# cfc-sensor-card.net
KiCad netlist of a schematic drawn in EAGLE
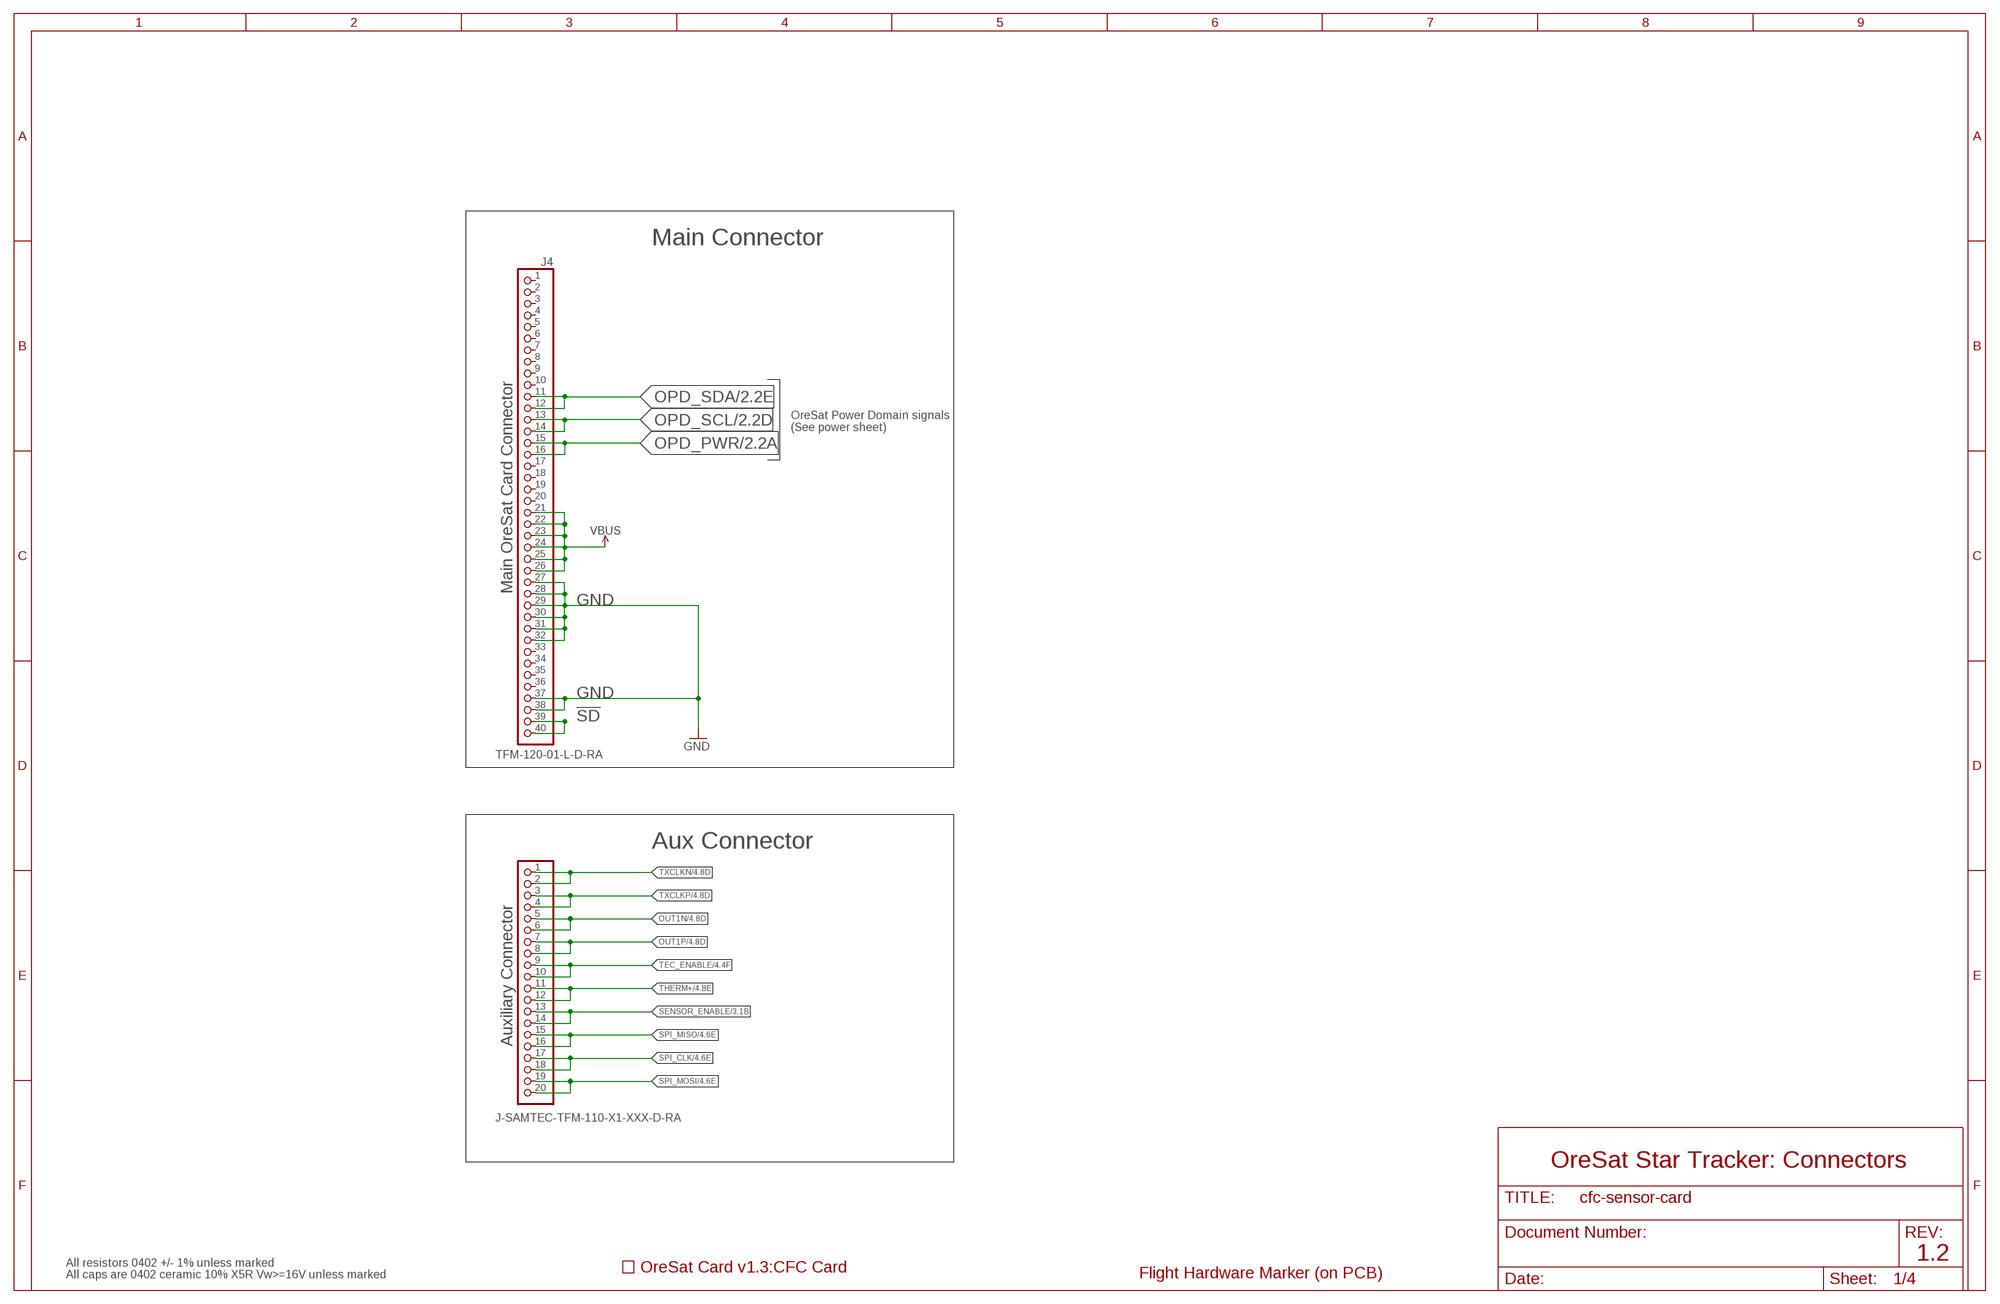
[diagram p0: schematic, sheet 1]
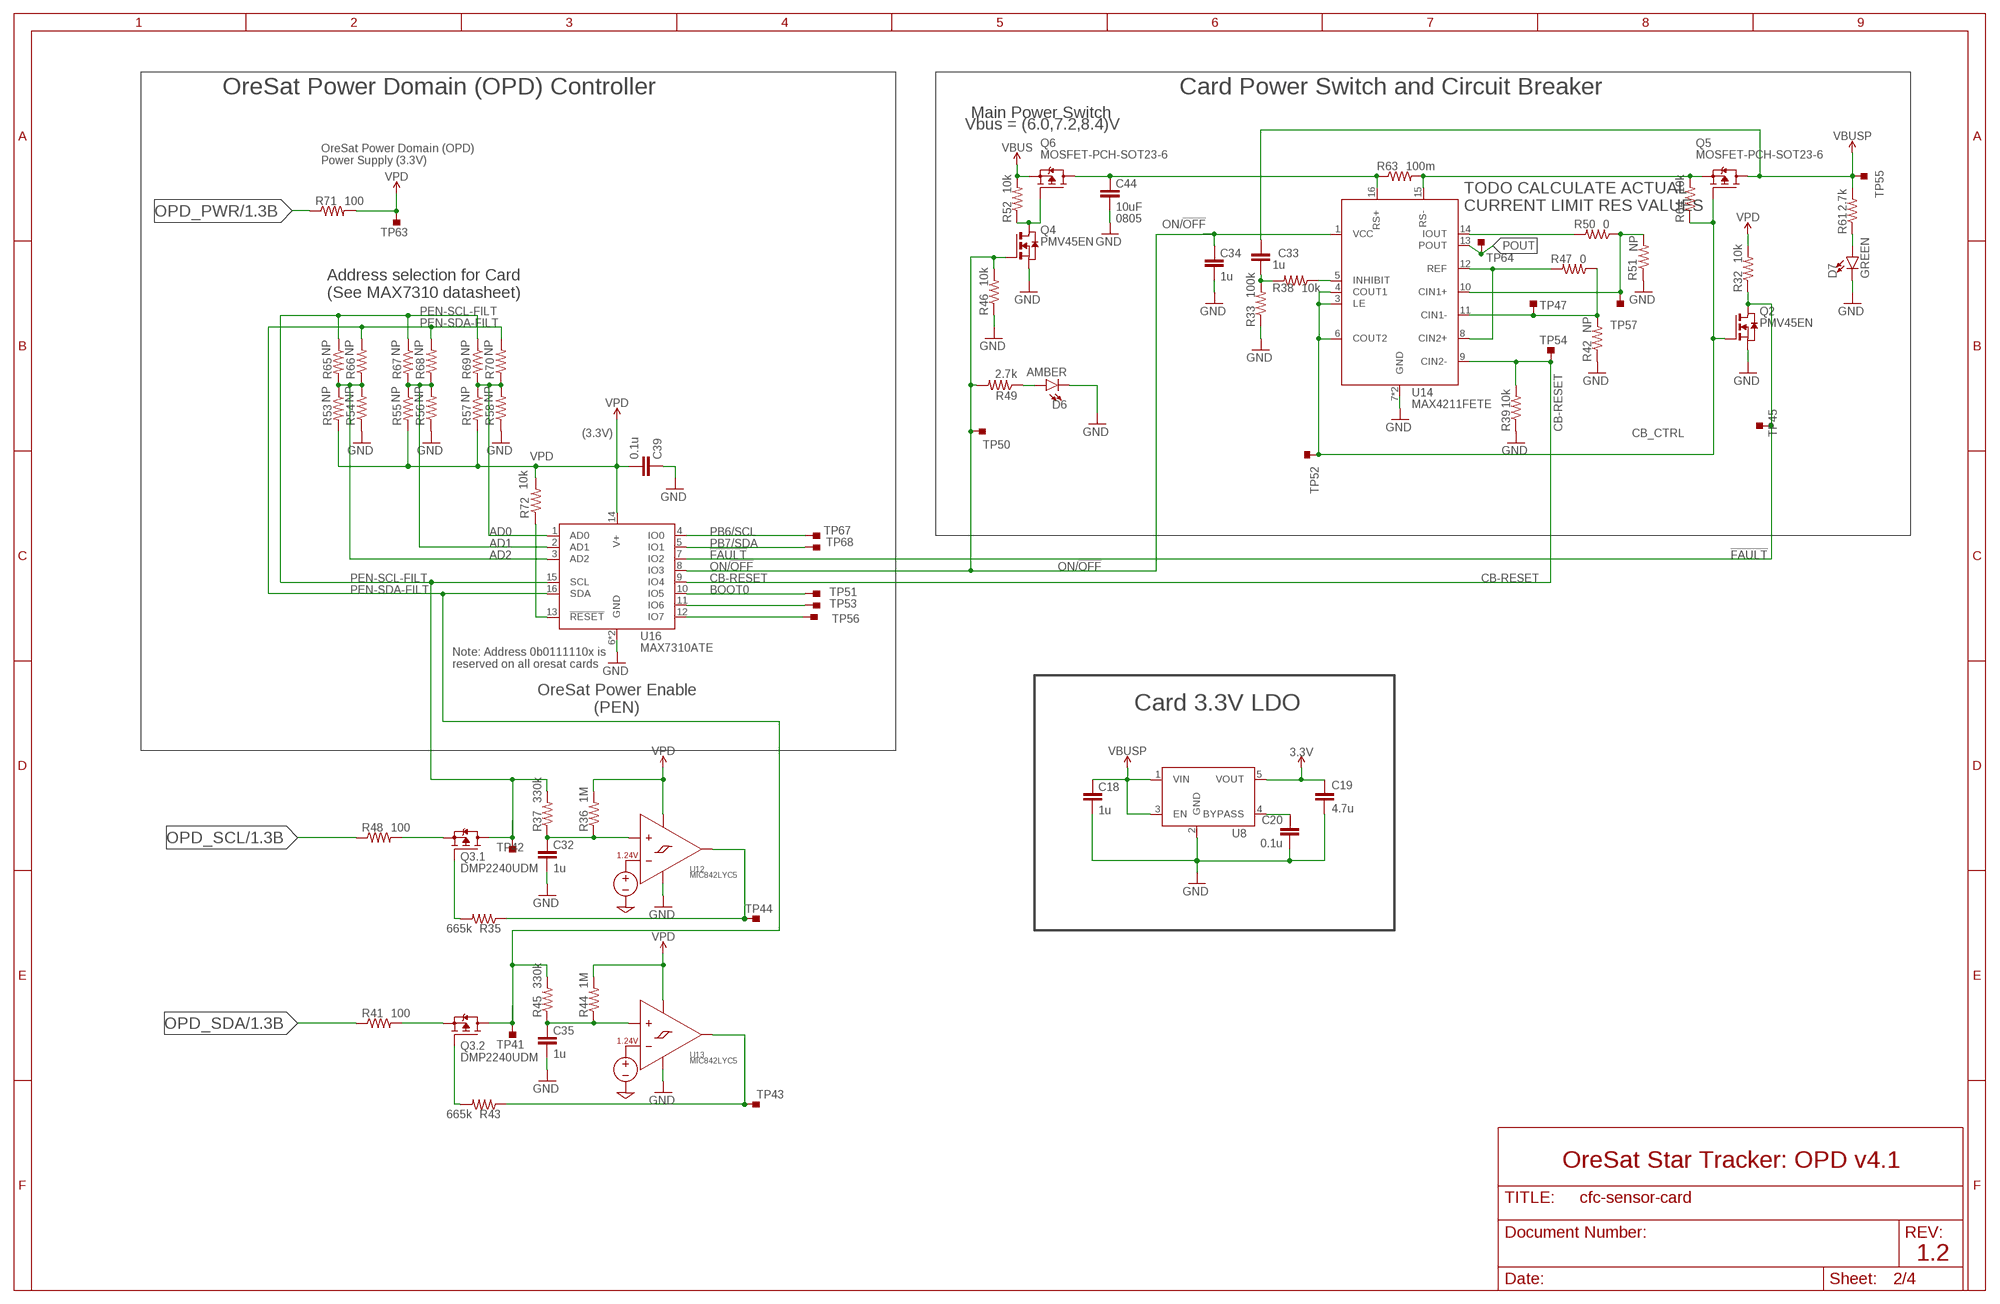
[diagram p1: schematic, sheet 2]
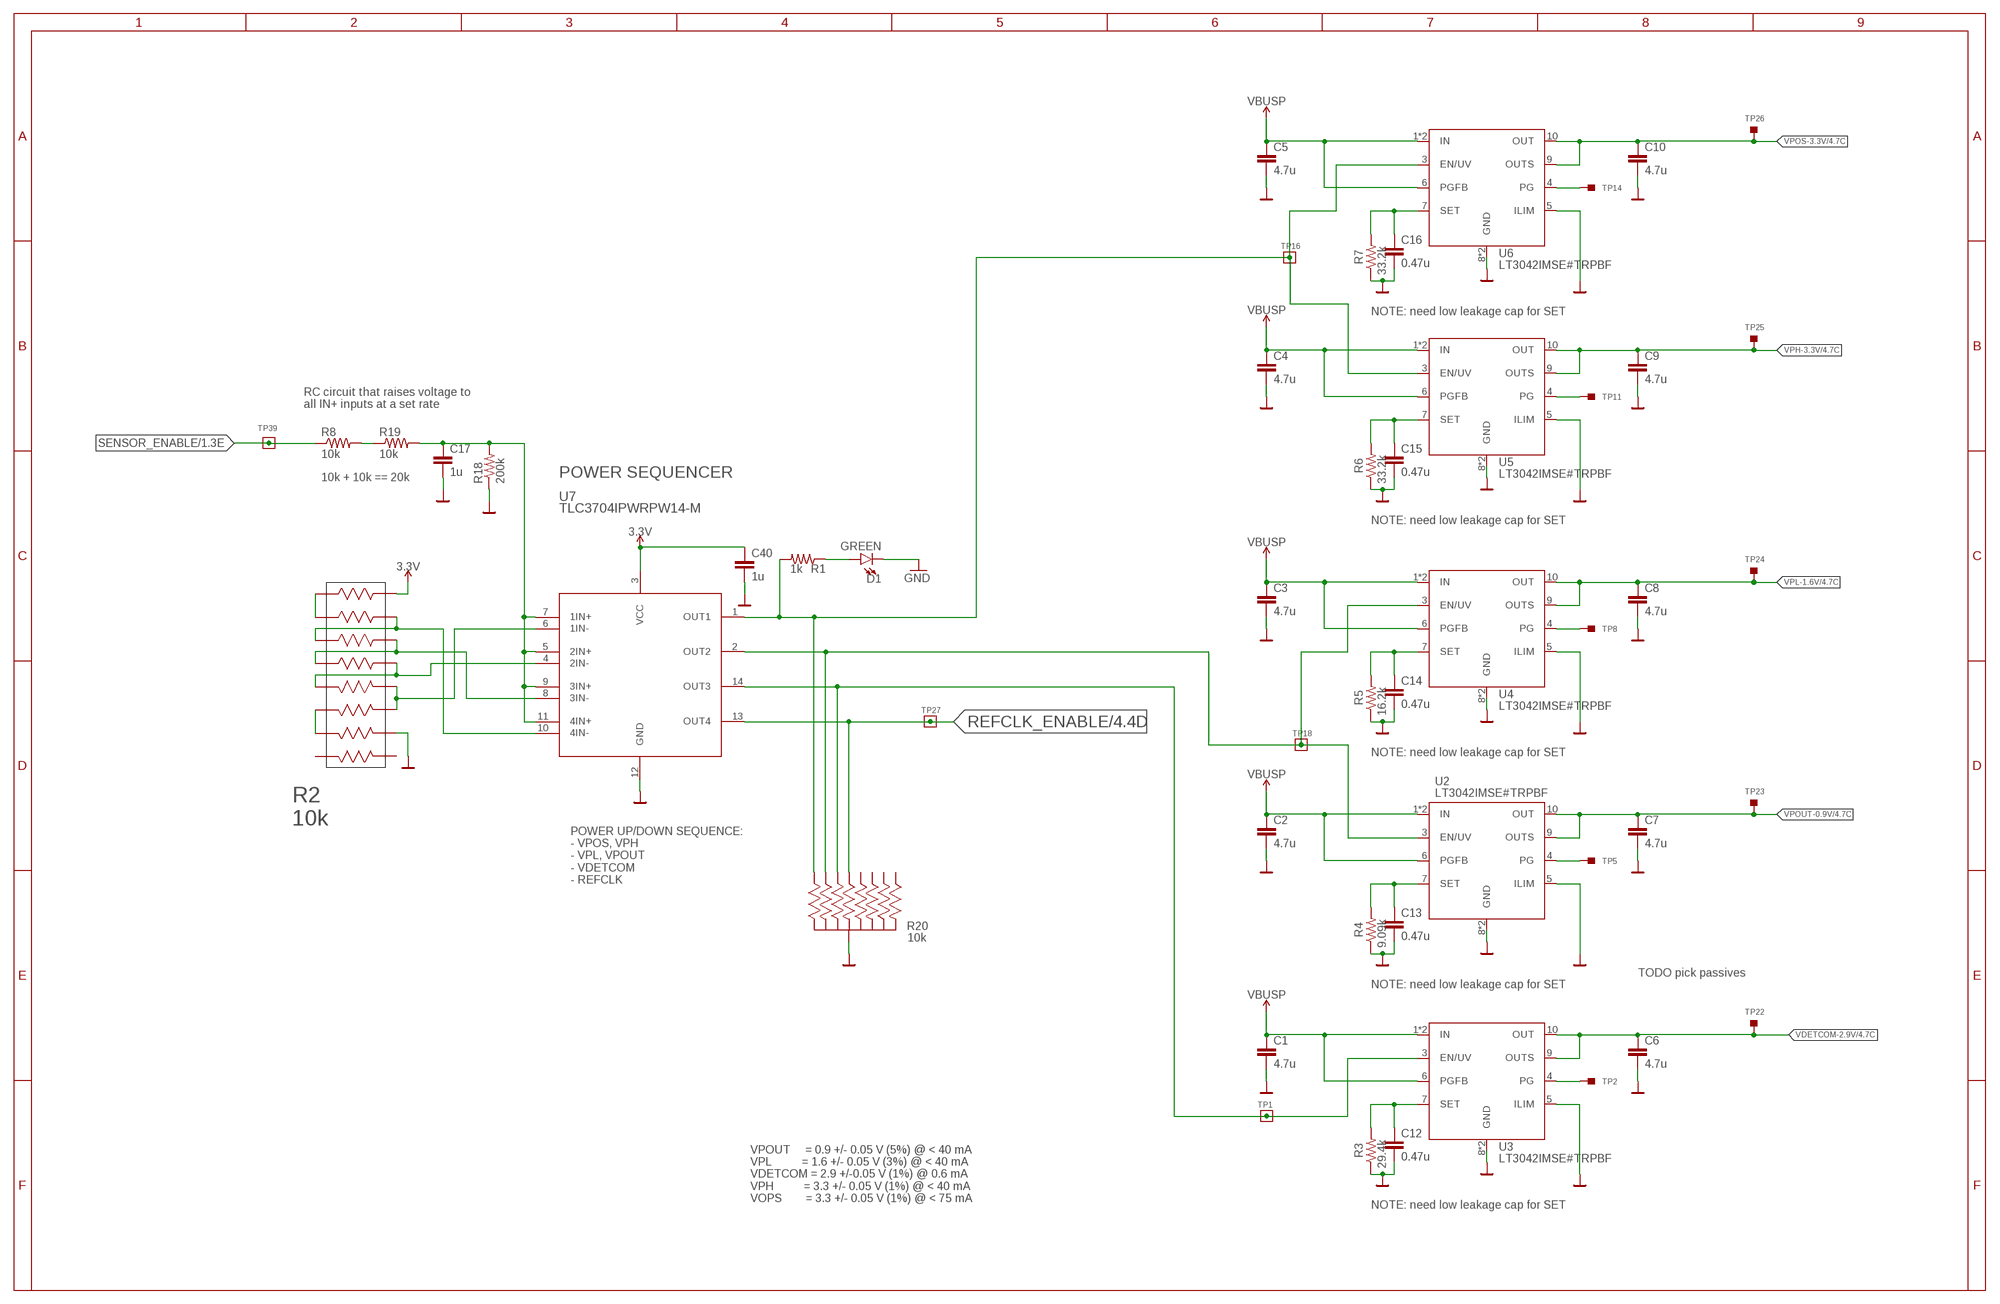
[diagram p2: schematic, sheet 3]
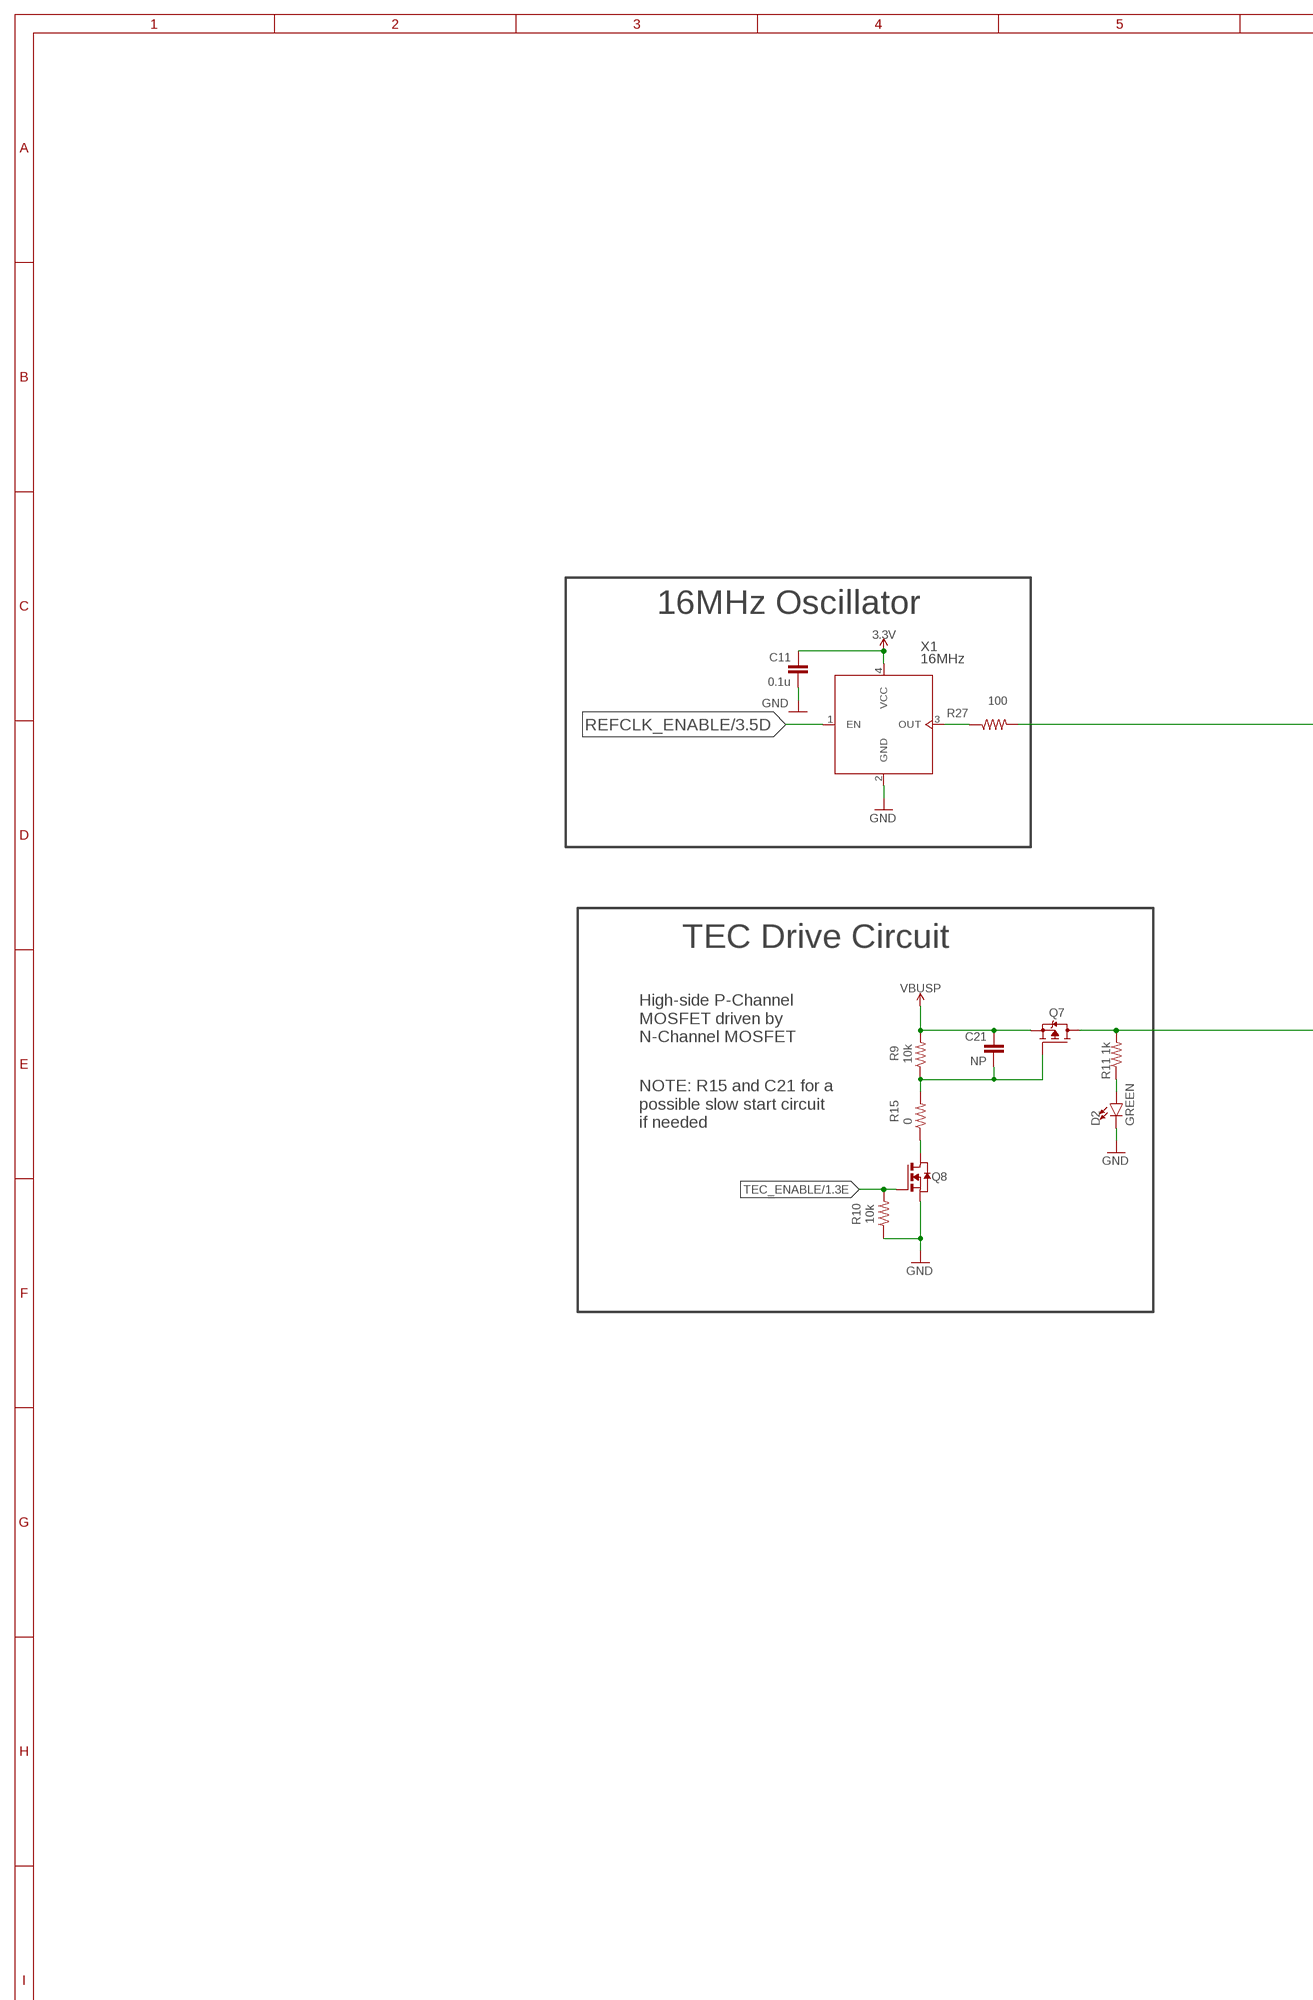
[diagram p3: schematic, sheet 4, part 1 of 2]
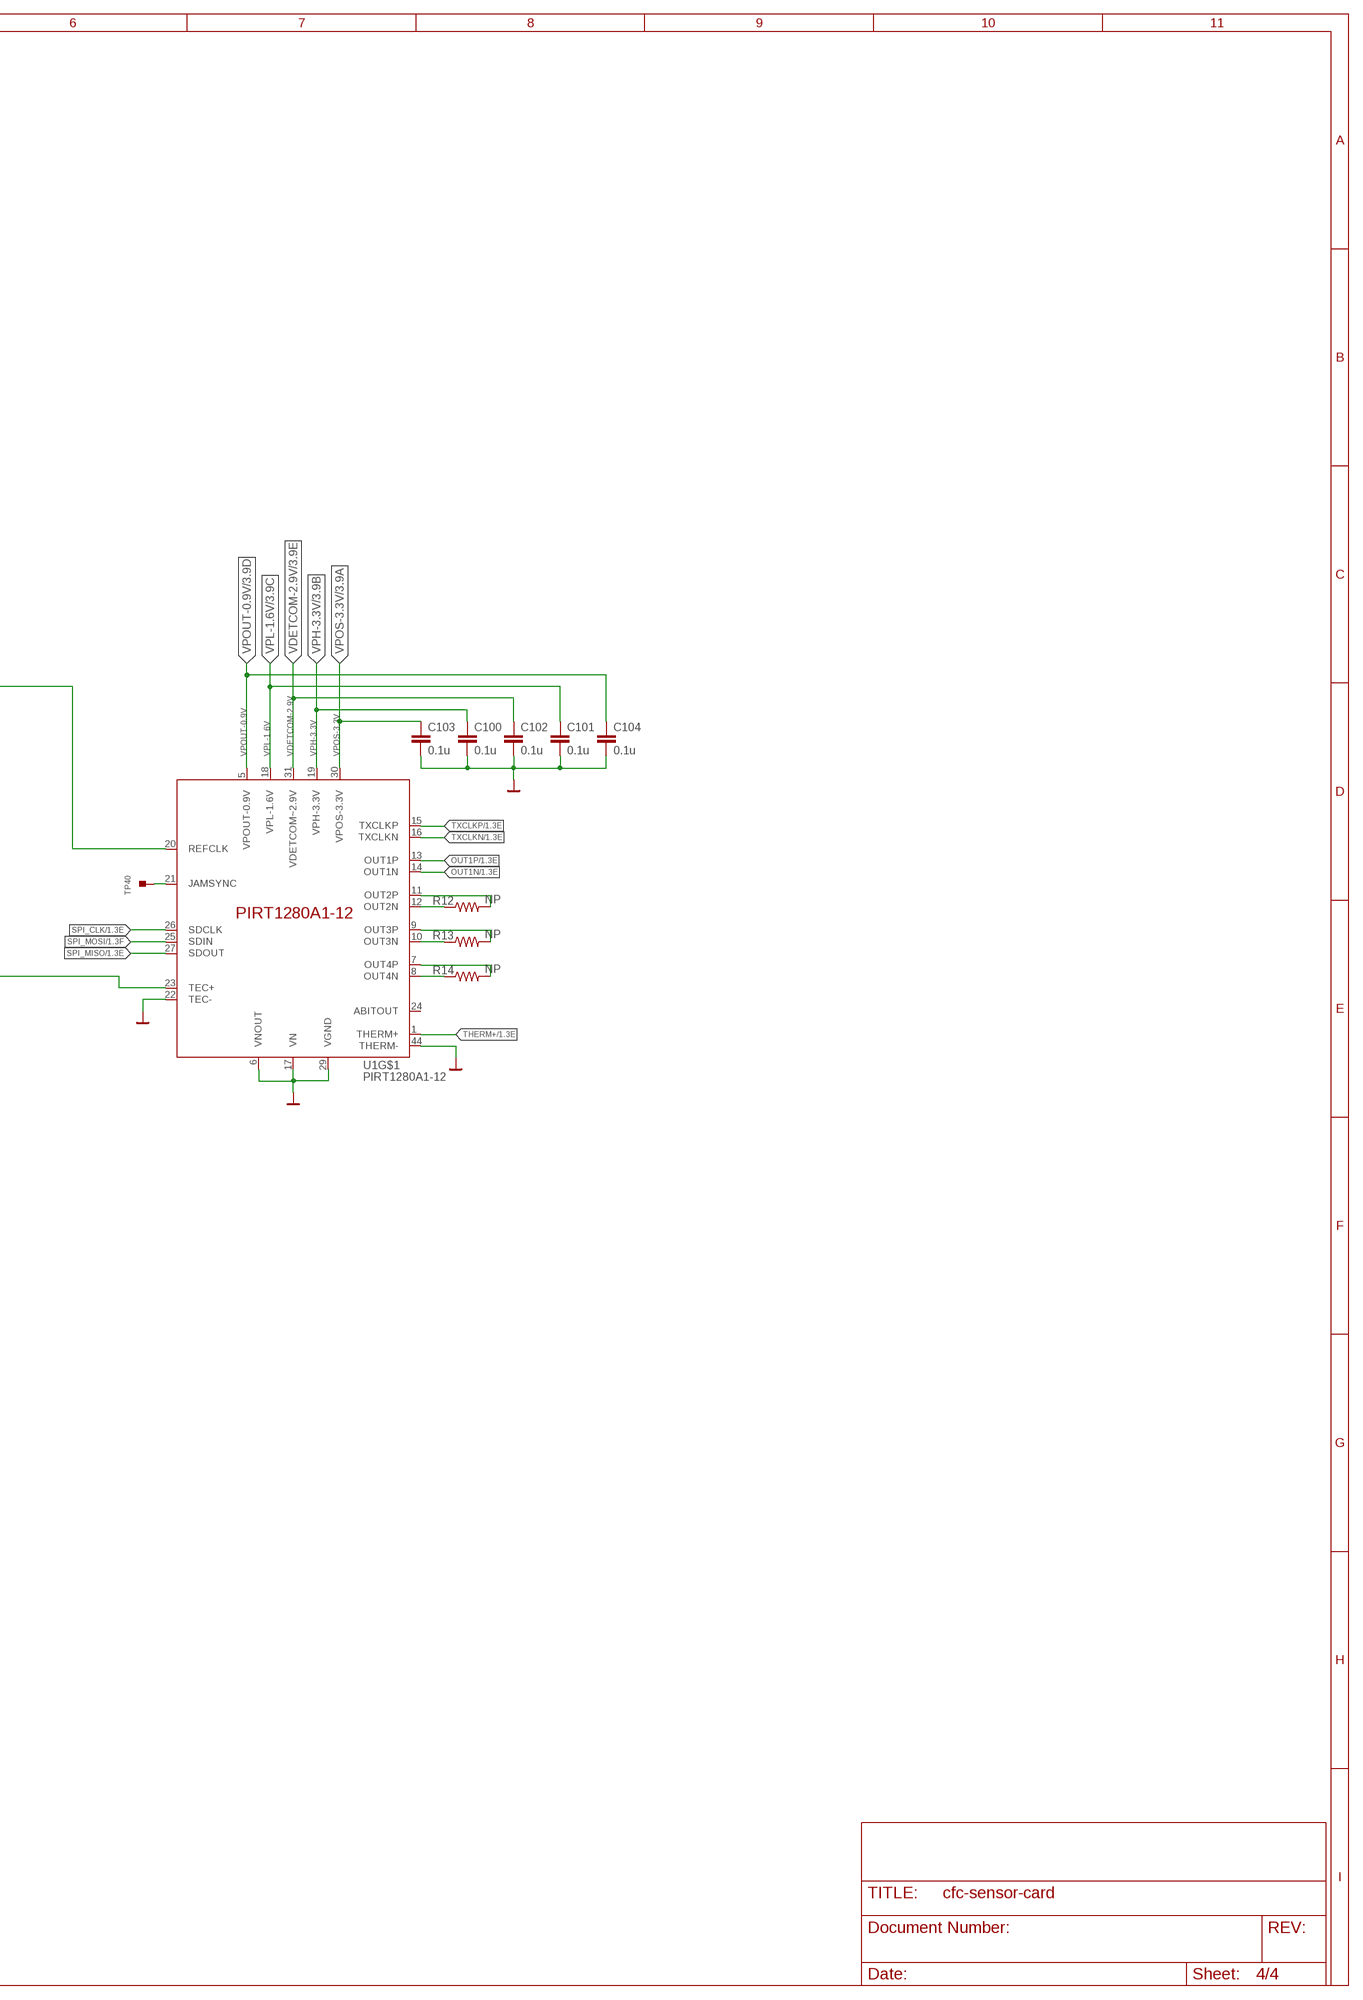
[diagram p4: schematic, sheet 4, part 2 of 2]

(export (version "E")
  (design (tool "Eeschema 10.0.6"))
  (components
    (comp (ref "C1")
      (value "4.7u")
      (footprint "eagle-import:.0603-B")
      (libsource (lib "eagle-import") (part "C-EU0603-B"))
    )
    (comp (ref "C2")
      (value "4.7u")
      (footprint "eagle-import:.0603-B")
      (libsource (lib "eagle-import") (part "C-EU0603-B"))
    )
    (comp (ref "C3")
      (value "4.7u")
      (footprint "eagle-import:.0603-B")
      (libsource (lib "eagle-import") (part "C-EU0603-B"))
    )
    (comp (ref "C4")
      (value "4.7u")
      (footprint "eagle-import:.0603-B")
      (libsource (lib "eagle-import") (part "C-EU0603-B"))
    )
    (comp (ref "C5")
      (value "4.7u")
      (footprint "eagle-import:.0603-B")
      (libsource (lib "eagle-import") (part "C-EU0603-B"))
    )
    (comp (ref "C6")
      (value "4.7u")
      (footprint "eagle-import:.0603-B")
      (libsource (lib "eagle-import") (part "C-EU0603-B"))
    )
    (comp (ref "C7")
      (value "4.7u")
      (footprint "eagle-import:.0603-B")
      (libsource (lib "eagle-import") (part "C-EU0603-B"))
    )
    (comp (ref "C8")
      (value "4.7u")
      (footprint "eagle-import:.0603-B")
      (libsource (lib "eagle-import") (part "C-EU0603-B"))
    )
    (comp (ref "C9")
      (value "4.7u")
      (footprint "eagle-import:.0603-B")
      (libsource (lib "eagle-import") (part "C-EU0603-B"))
    )
    (comp (ref "C10")
      (value "4.7u")
      (footprint "eagle-import:.0603-B")
      (libsource (lib "eagle-import") (part "C-EU0603-B"))
    )
    (comp (ref "C12")
      (value "0.47u")
      (footprint "eagle-import:.0603-B")
      (libsource (lib "eagle-import") (part "C-EU0603-B"))
    )
    (comp (ref "C13")
      (value "0.47u")
      (footprint "eagle-import:.0603-B")
      (libsource (lib "eagle-import") (part "C-EU0603-B"))
    )
    (comp (ref "C14")
      (value "0.47u")
      (footprint "eagle-import:.0603-B")
      (libsource (lib "eagle-import") (part "C-EU0603-B"))
    )
    (comp (ref "C15")
      (value "0.47u")
      (footprint "eagle-import:.0603-B")
      (libsource (lib "eagle-import") (part "C-EU0603-B"))
    )
    (comp (ref "C16")
      (value "0.47u")
      (footprint "eagle-import:.0603-B")
      (libsource (lib "eagle-import") (part "C-EU0603-B"))
    )
    (comp (ref "C17")
      (value "1u")
      (footprint "eagle-import:.0603-B")
      (libsource (lib "eagle-import") (part "C-EU0603-B"))
    )
    (comp (ref "C40")
      (value "1u")
      (footprint "eagle-import:.0603-B")
      (libsource (lib "eagle-import") (part "C-EU0603-B"))
    )
    (comp (ref "D1")
      (value "GREEN")
      (footprint "eagle-import:LED-0603")
      (description "Green 573nm LED Indication - Discrete 2V 0603 (1608 Metric)")
      (fields
        (field (name "DIGI-KEY_PART_NUMBER") "732-12017-1-ND")
        (field (name "MANUFACTURER") "Würth Elektronik")
      )
      (libsource (lib "eagle-import") (part "LED-GREEN0603"))
    )
    (comp (ref "R1")
      (value "1k")
      (footprint "eagle-import:.0603-B")
      (libsource (lib "eagle-import") (part "R-US_0603-B"))
    )
    (comp (ref "R2")
      (value "10k")
      (footprint "eagle-import:RES_EXB2HV")
      (fields (field (name "MPN") "EXB-2HV103JV"))
      (libsource (lib "eagle-import") (part "EXB-2HV103JV-LEGACY"))
    )
    (comp (ref "R3")
      (value "29.4k")
      (footprint "eagle-import:.0603-B")
      (libsource (lib "eagle-import") (part "R-US_0603-B"))
    )
    (comp (ref "R4")
      (value "9.09k")
      (footprint "eagle-import:.0603-B")
      (libsource (lib "eagle-import") (part "R-US_0603-B"))
    )
    (comp (ref "R5")
      (value "16.2k")
      (footprint "eagle-import:.0603-B")
      (libsource (lib "eagle-import") (part "R-US_0603-B"))
    )
    (comp (ref "R6")
      (value "33.2k")
      (footprint "eagle-import:.0603-B")
      (libsource (lib "eagle-import") (part "R-US_0603-B"))
    )
    (comp (ref "R7")
      (value "33.2k")
      (footprint "eagle-import:.0603-B")
      (libsource (lib "eagle-import") (part "R-US_0603-B"))
    )
    (comp (ref "R8")
      (value "10k")
      (footprint "eagle-import:.0603-B")
      (libsource (lib "eagle-import") (part "R-US_0603-B"))
    )
    (comp (ref "R18")
      (value "200k")
      (footprint "eagle-import:.0603-B")
      (libsource (lib "eagle-import") (part "R-US_0603-B"))
    )
    (comp (ref "R19")
      (value "10k")
      (footprint "eagle-import:.0603-B")
      (libsource (lib "eagle-import") (part "R-US_0603-B"))
    )
    (comp (ref "R20")
      (value "10k")
      (footprint "eagle-import:ARRAY_EXBA-M")
      (fields (field (name "MFR") "Panasonic Electronic Components") (field (name "MPN") "EXB-A10P103J"))
      (libsource (lib "eagle-import") (part "EXB-A10P391JC_ARRAY_EXBA-M"))
    )
    (comp (ref "TP1")
      (value "TEST-POINT-LARGE-SQUARE")
      (footprint "eagle-import:1X01")
      (libsource (lib "eagle-import") (part "TEST-POINT-LARGE-SQUARE"))
    )
    (comp (ref "TP2")
      (value "TEST-POINT_SMD-SMD-10SN")
      (footprint "eagle-import:TESTPOINT_SMD-10SN")
      (libsource (lib "eagle-import") (part "TEST-POINT_SMD-SMD-10SN"))
    )
    (comp (ref "TP5")
      (value "TEST-POINT_SMD-SMD-10SN")
      (footprint "eagle-import:TESTPOINT_SMD-10SN")
      (libsource (lib "eagle-import") (part "TEST-POINT_SMD-SMD-10SN"))
    )
    (comp (ref "TP8")
      (value "TEST-POINT_SMD-SMD-10SN")
      (footprint "eagle-import:TESTPOINT_SMD-10SN")
      (libsource (lib "eagle-import") (part "TEST-POINT_SMD-SMD-10SN"))
    )
    (comp (ref "TP11")
      (value "TEST-POINT_SMD-SMD-10SN")
      (footprint "eagle-import:TESTPOINT_SMD-10SN")
      (libsource (lib "eagle-import") (part "TEST-POINT_SMD-SMD-10SN"))
    )
    (comp (ref "TP14")
      (value "TEST-POINT_SMD-SMD-10SN")
      (footprint "eagle-import:TESTPOINT_SMD-10SN")
      (libsource (lib "eagle-import") (part "TEST-POINT_SMD-SMD-10SN"))
    )
    (comp (ref "TP16")
      (value "TEST-POINT-LARGE-SQUARE")
      (footprint "eagle-import:1X01")
      (libsource (lib "eagle-import") (part "TEST-POINT-LARGE-SQUARE"))
    )
    (comp (ref "TP18")
      (value "TEST-POINT-LARGE-SQUARE")
      (footprint "eagle-import:1X01")
      (libsource (lib "eagle-import") (part "TEST-POINT-LARGE-SQUARE"))
    )
    (comp (ref "TP22")
      (value "TEST-POINT_SMD-SMD-10SN")
      (footprint "eagle-import:TESTPOINT_SMD-10SN")
      (libsource (lib "eagle-import") (part "TEST-POINT_SMD-SMD-10SN"))
    )
    (comp (ref "TP23")
      (value "TEST-POINT_SMD-SMD-10SN")
      (footprint "eagle-import:TESTPOINT_SMD-10SN")
      (libsource (lib "eagle-import") (part "TEST-POINT_SMD-SMD-10SN"))
    )
    (comp (ref "TP24")
      (value "TEST-POINT_SMD-SMD-10SN")
      (footprint "eagle-import:TESTPOINT_SMD-10SN")
      (libsource (lib "eagle-import") (part "TEST-POINT_SMD-SMD-10SN"))
    )
    (comp (ref "TP25")
      (value "TEST-POINT_SMD-SMD-10SN")
      (footprint "eagle-import:TESTPOINT_SMD-10SN")
      (libsource (lib "eagle-import") (part "TEST-POINT_SMD-SMD-10SN"))
    )
    (comp (ref "TP26")
      (value "TEST-POINT_SMD-SMD-10SN")
      (footprint "eagle-import:TESTPOINT_SMD-10SN")
      (libsource (lib "eagle-import") (part "TEST-POINT_SMD-SMD-10SN"))
    )
    (comp (ref "TP27")
      (value "TEST-POINT-LARGE-SQUARE")
      (footprint "eagle-import:1X01")
      (libsource (lib "eagle-import") (part "TEST-POINT-LARGE-SQUARE"))
    )
    (comp (ref "TP39")
      (value "TEST-POINT-LARGE-SQUARE")
      (footprint "eagle-import:1X01")
      (libsource (lib "eagle-import") (part "TEST-POINT-LARGE-SQUARE"))
    )
    (comp (ref "U2")
      (value "LT3042IMSE#TRPBF")
      (footprint "eagle-import:SOP50P490X110-11N")
      (fields (field (name "MF") "Analog Devices"))
      (libsource (lib "eagle-import") (part "LT3042IMSE#TRPBF"))
    )
    (comp (ref "U3")
      (value "LT3042IMSE#TRPBF")
      (footprint "eagle-import:SOP50P490X110-11N")
      (fields (field (name "MF") "Analog Devices"))
      (libsource (lib "eagle-import") (part "LT3042IMSE#TRPBF"))
    )
    (comp (ref "U4")
      (value "LT3042IMSE#TRPBF")
      (footprint "eagle-import:SOP50P490X110-11N")
      (fields (field (name "MF") "Analog Devices"))
      (libsource (lib "eagle-import") (part "LT3042IMSE#TRPBF"))
    )
    (comp (ref "U5")
      (value "LT3042IMSE#TRPBF")
      (footprint "eagle-import:SOP50P490X110-11N")
      (fields (field (name "MF") "Analog Devices"))
      (libsource (lib "eagle-import") (part "LT3042IMSE#TRPBF"))
    )
    (comp (ref "U6")
      (value "LT3042IMSE#TRPBF")
      (footprint "eagle-import:SOP50P490X110-11N")
      (fields (field (name "MF") "Analog Devices"))
      (libsource (lib "eagle-import") (part "LT3042IMSE#TRPBF"))
    )
    (comp (ref "U7")
      (value "TLC3704IPWRPW14-M")
      (footprint "eagle-import:14-TSSOP")
      (fields
        (field (name "GENERIC_PART_NUMBER") "LM2901-Q1")
        (field (name "MANUFACTURER") "Texas Instruments")
        (field (name "MPN") "LM2901QPWRQ1")
      )
      (libsource (lib "eagle-import") (part "TLC3704IPWRPW14-M"))
    )
    (comp (ref "C18")
      (value "1u")
      (footprint "eagle-import:.0603-B")
      (libsource (lib "eagle-import") (part "C-EU0603-B"))
    )
    (comp (ref "C19")
      (value "4.7u")
      (footprint "eagle-import:.0603-B")
      (libsource (lib "eagle-import") (part "C-EU0603-B"))
    )
    (comp (ref "C20")
      (value "0.1u")
      (footprint "eagle-import:.0603-B")
      (libsource (lib "eagle-import") (part "C-EU0603-B"))
    )
    (comp (ref "C32")
      (value "1u")
      (footprint "eagle-import:.0603-B")
      (libsource (lib "eagle-import") (part "C-EU0603-B"))
    )
    (comp (ref "C33")
      (value "1u")
      (footprint "eagle-import:.0603-B")
      (libsource (lib "eagle-import") (part "C-EU0603-B"))
    )
    (comp (ref "C34")
      (value "1u")
      (footprint "eagle-import:.0603-B")
      (libsource (lib "eagle-import") (part "C-EU0603-B"))
    )
    (comp (ref "C35")
      (value "1u")
      (footprint "eagle-import:.0603-B")
      (libsource (lib "eagle-import") (part "C-EU0603-B"))
    )
    (comp (ref "C39")
      (value "0.1u")
      (footprint "eagle-import:.0603-B")
      (libsource (lib "eagle-import") (part "C-EU0603-B"))
    )
    (comp (ref "C44")
      (value "10uF")
      (footprint "eagle-import:.0603-B")
      (libsource (lib "eagle-import") (part "C-EU0603-B"))
    )
    (comp (ref "D6")
      (value "AMBER")
      (footprint "eagle-import:LED-0603")
      (libsource (lib "eagle-import") (part "SparkFun-LED_529_LED-GREEN0603"))
    )
    (comp (ref "D7")
      (value "GREEN")
      (footprint "eagle-import:LED-0603")
      (libsource (lib "eagle-import") (part "LED-GREEN0603"))
    )
    (comp (ref "Q2")
      (value "PMV45EN")
      (footprint "eagle-import:SOT23")
      (fields (field (name "MPN") "PMV45EN2R"))
      (libsource (lib "eagle-import") (part "PMV45EN"))
    )
    (comp (ref "Q3")
      (value "DMP2240UDM")
      (footprint "eagle-import:SOT23-6")
      (fields (field (name "MFR") "Diodes Inc") (field (name "MPN") "DMP2240UDM-7"))
      (libsource (lib "eagle-import") (part "Q-MOSFET-PCH-dual-SOT23-6_MOSFET-PCH-SOT23-6"))
    )
    (comp (ref "Q4")
      (value "PMV45EN")
      (footprint "eagle-import:SOT23")
      (fields (field (name "MPN") "PMV45EN2R"))
      (libsource (lib "eagle-import") (part "PMV45EN"))
    )
    (comp (ref "Q5")
      (value "MOSFET-PCH-SOT23-6")
      (footprint "eagle-import:SOT23-6")
      (fields (field (name "MPN") "DMP3050LVT-7") (field (name "MPN_1") "DMP3050LVT-7"))
      (libsource (lib "eagle-import") (part "MOSFET-PCH-SOT23-6"))
    )
    (comp (ref "Q6")
      (value "MOSFET-PCH-SOT23-6")
      (footprint "eagle-import:SOT23-6")
      (fields (field (name "MPN") "DMP3050LVT-7") (field (name "MPN_1") "DMP3050LVT-7"))
      (libsource (lib "eagle-import") (part "MOSFET-PCH-SOT23-6"))
    )
    (comp (ref "R32")
      (value "10k")
      (footprint "eagle-import:.0603-B")
      (libsource (lib "eagle-import") (part "R-US_0603-B"))
    )
    (comp (ref "R33")
      (value "100k")
      (footprint "eagle-import:.0603-B")
      (fields (field (name "MFR") "Samsung") (field (name "MPN") "RC1005F6653CS"))
      (libsource (lib "eagle-import") (part "R-US_0603-B"))
    )
    (comp (ref "R35")
      (value "665k")
      (footprint "eagle-import:.0603-B")
      (libsource (lib "eagle-import") (part "R-US_0603-B"))
    )
    (comp (ref "R36")
      (value "1M")
      (footprint "eagle-import:.0603-B")
      (libsource (lib "eagle-import") (part "R-US_0603-B"))
    )
    (comp (ref "R37")
      (value "330k")
      (footprint "eagle-import:.0603-B")
      (libsource (lib "eagle-import") (part "R-US_0603-B"))
    )
    (comp (ref "R38")
      (value "10k")
      (footprint "eagle-import:.0603-B")
      (fields (field (name "MFR") "Samsung") (field (name "MPN") "RC1005F6653CS"))
      (libsource (lib "eagle-import") (part "R-US_0603-B"))
    )
    (comp (ref "R39")
      (value "10k")
      (footprint "eagle-import:.0603-B")
      (libsource (lib "eagle-import") (part "R-US_0603-B"))
    )
    (comp (ref "R41")
      (value "100")
      (footprint "eagle-import:.0603-B")
      (libsource (lib "eagle-import") (part "R-US_0603-B"))
    )
    (comp (ref "R42")
      (value "NP")
      (footprint "eagle-import:.0603-B")
      (fields (field (name "MFR") "Samsung") (field (name "MPN") "RC1005F6653CS"))
      (libsource (lib "eagle-import") (part "R-US_0603-B"))
    )
    (comp (ref "R43")
      (value "665k")
      (footprint "eagle-import:.0603-B")
      (libsource (lib "eagle-import") (part "R-US_0603-B"))
    )
    (comp (ref "R44")
      (value "1M")
      (footprint "eagle-import:.0603-B")
      (libsource (lib "eagle-import") (part "R-US_0603-B"))
    )
    (comp (ref "R45")
      (value "330k")
      (footprint "eagle-import:.0603-B")
      (libsource (lib "eagle-import") (part "R-US_0603-B"))
    )
    (comp (ref "R46")
      (value "10k")
      (footprint "eagle-import:.0603-B")
      (libsource (lib "eagle-import") (part "R-US_0603-B"))
    )
    (comp (ref "R47")
      (value "0")
      (footprint "eagle-import:.0603-B")
      (libsource (lib "eagle-import") (part "R-US_0603-B"))
    )
    (comp (ref "R48")
      (value "100")
      (footprint "eagle-import:.0603-B")
      (libsource (lib "eagle-import") (part "R-US_0603-B"))
    )
    (comp (ref "R49")
      (value "2.7k")
      (footprint "eagle-import:.0603-B")
      (libsource (lib "eagle-import") (part "R-US_0603-B"))
    )
    (comp (ref "R50")
      (value "0")
      (footprint "eagle-import:.0603-B")
      (libsource (lib "eagle-import") (part "R-US_0603-B"))
    )
    (comp (ref "R51")
      (value "NP")
      (footprint "eagle-import:.0603-B")
      (fields (field (name "MFR") "Samsung") (field (name "MPN") "RC1005F6653CS"))
      (libsource (lib "eagle-import") (part "R-US_0603-B"))
    )
    (comp (ref "R52")
      (value "10k")
      (footprint "eagle-import:.0603-B")
      (libsource (lib "eagle-import") (part "R-US_0603-B"))
    )
    (comp (ref "R53")
      (value "NP")
      (footprint "eagle-import:.0603-B")
      (fields (field (name "MFR") "Samsung") (field (name "MPN") "RC1005F6653CS"))
      (libsource (lib "eagle-import") (part "R-US_0603-B"))
    )
    (comp (ref "R54")
      (value "NP")
      (footprint "eagle-import:.0603-B")
      (fields (field (name "MFR") "Samsung") (field (name "MPN") "RC1005F6653CS"))
      (libsource (lib "eagle-import") (part "R-US_0603-B"))
    )
    (comp (ref "R55")
      (value "NP")
      (footprint "eagle-import:.0603-B")
      (fields (field (name "MFR") "Samsung") (field (name "MPN") "RC1005F6653CS"))
      (libsource (lib "eagle-import") (part "R-US_0603-B"))
    )
    (comp (ref "R56")
      (value "NP")
      (footprint "eagle-import:.0603-B")
      (fields (field (name "MFR") "Samsung") (field (name "MPN") "RC1005F6653CS"))
      (libsource (lib "eagle-import") (part "R-US_0603-B"))
    )
    (comp (ref "R57")
      (value "NP")
      (footprint "eagle-import:.0603-B")
      (fields (field (name "MFR") "Samsung") (field (name "MPN") "RC1005F6653CS"))
      (libsource (lib "eagle-import") (part "R-US_0603-B"))
    )
    (comp (ref "R58")
      (value "NP")
      (footprint "eagle-import:.0603-B")
      (fields (field (name "MFR") "Samsung") (field (name "MPN") "RC1005F6653CS"))
      (libsource (lib "eagle-import") (part "R-US_0603-B"))
    )
    (comp (ref "R61")
      (value "2.7k")
      (footprint "eagle-import:.0603-B")
      (libsource (lib "eagle-import") (part "R-US_0603-B"))
    )
    (comp (ref "R63")
      (value "100m")
      (footprint "eagle-import:R1206")
      (libsource (lib "eagle-import") (part "rcl_334_R-US_R1206"))
    )
    (comp (ref "R64")
      (value "10k")
      (footprint "eagle-import:.0603-B")
      (libsource (lib "eagle-import") (part "R-US_0603-B"))
    )
    (comp (ref "R65")
      (value "NP")
      (footprint "eagle-import:.0603-B")
      (fields (field (name "MFR") "Samsung") (field (name "MPN") "RC1005F6653CS"))
      (libsource (lib "eagle-import") (part "R-US_0603-B"))
    )
    (comp (ref "R66")
      (value "NP")
      (footprint "eagle-import:.0603-B")
      (fields (field (name "MFR") "Samsung") (field (name "MPN") "RC1005F6653CS"))
      (libsource (lib "eagle-import") (part "R-US_0603-B"))
    )
    (comp (ref "R67")
      (value "NP")
      (footprint "eagle-import:.0603-B")
      (fields (field (name "MFR") "Samsung") (field (name "MPN") "RC1005F6653CS"))
      (libsource (lib "eagle-import") (part "R-US_0603-B"))
    )
    (comp (ref "R68")
      (value "NP")
      (footprint "eagle-import:.0603-B")
      (fields (field (name "MFR") "Samsung") (field (name "MPN") "RC1005F6653CS"))
      (libsource (lib "eagle-import") (part "R-US_0603-B"))
    )
    (comp (ref "R69")
      (value "NP")
      (footprint "eagle-import:.0603-B")
      (fields (field (name "MFR") "Samsung") (field (name "MPN") "RC1005F6653CS"))
      (libsource (lib "eagle-import") (part "R-US_0603-B"))
    )
    (comp (ref "R70")
      (value "NP")
      (footprint "eagle-import:.0603-B")
      (fields (field (name "MFR") "Samsung") (field (name "MPN") "RC1005F6653CS"))
      (libsource (lib "eagle-import") (part "R-US_0603-B"))
    )
    (comp (ref "R71")
      (value "100")
      (footprint "eagle-import:.0603-B")
      (libsource (lib "eagle-import") (part "R-US_0603-B"))
    )
    (comp (ref "R72")
      (value "10k")
      (footprint "eagle-import:.0603-B")
      (libsource (lib "eagle-import") (part "R-US_0603-B"))
    )
    (comp (ref "TP41")
      (value "TEST-POINT_SMD-SMD-10SN")
      (footprint "eagle-import:TESTPOINT_SMD-10SN")
      (libsource (lib "eagle-import") (part "TEST-POINT_SMD-SMD-10SN"))
    )
    (comp (ref "TP42")
      (value "TEST-POINT_SMD-SMD-10SN")
      (footprint "eagle-import:TESTPOINT_SMD-10SN")
      (libsource (lib "eagle-import") (part "TEST-POINT_SMD-SMD-10SN"))
    )
    (comp (ref "TP43")
      (value "TEST-POINT_SMD-SMD-10SN")
      (footprint "eagle-import:TESTPOINT_SMD-10SN")
      (libsource (lib "eagle-import") (part "TEST-POINT_SMD-SMD-10SN"))
    )
    (comp (ref "TP44")
      (value "TEST-POINT_SMD-SMD-10SN")
      (footprint "eagle-import:TESTPOINT_SMD-10SN")
      (libsource (lib "eagle-import") (part "TEST-POINT_SMD-SMD-10SN"))
    )
    (comp (ref "TP45")
      (value "TEST-POINT_SMD-SMD-10SN")
      (footprint "eagle-import:TESTPOINT_SMD-10SN")
      (libsource (lib "eagle-import") (part "TEST-POINT_SMD-SMD-10SN"))
    )
    (comp (ref "TP47")
      (value "TEST-POINT_SMD-SMD-10SN")
      (footprint "eagle-import:TESTPOINT_SMD-10SN")
      (libsource (lib "eagle-import") (part "TEST-POINT_SMD-SMD-10SN"))
    )
    (comp (ref "TP50")
      (value "TEST-POINT_SMD-SMD-10SN")
      (footprint "eagle-import:TESTPOINT_SMD-10SN")
      (libsource (lib "eagle-import") (part "TEST-POINT_SMD-SMD-10SN"))
    )
    (comp (ref "TP51")
      (value "TEST-POINT_SMD-SMD-10SN")
      (footprint "eagle-import:TESTPOINT_SMD-10SN")
      (libsource (lib "eagle-import") (part "TEST-POINT_SMD-SMD-10SN"))
    )
    (comp (ref "TP52")
      (value "TEST-POINT_SMD-SMD-10SN")
      (footprint "eagle-import:TESTPOINT_SMD-10SN")
      (libsource (lib "eagle-import") (part "TEST-POINT_SMD-SMD-10SN"))
    )
    (comp (ref "TP53")
      (value "TEST-POINT_SMD-SMD-10SN")
      (footprint "eagle-import:TESTPOINT_SMD-10SN")
      (libsource (lib "eagle-import") (part "TEST-POINT_SMD-SMD-10SN"))
    )
    (comp (ref "TP54")
      (value "TEST-POINT_SMD-SMD-10SN")
      (footprint "eagle-import:TESTPOINT_SMD-10SN")
      (libsource (lib "eagle-import") (part "TEST-POINT_SMD-SMD-10SN"))
    )
    (comp (ref "TP55")
      (value "TEST-POINT_SMD-SMD-10SN")
      (footprint "eagle-import:TESTPOINT_SMD-10SN")
      (libsource (lib "eagle-import") (part "TEST-POINT_SMD-SMD-10SN"))
    )
    (comp (ref "TP56")
      (value "TEST-POINT_SMD-SMD-10SN")
      (footprint "eagle-import:TESTPOINT_SMD-10SN")
      (libsource (lib "eagle-import") (part "TEST-POINT_SMD-SMD-10SN"))
    )
    (comp (ref "TP57")
      (value "TEST-POINT_SMD-SMD-10SN")
      (footprint "eagle-import:TESTPOINT_SMD-10SN")
      (libsource (lib "eagle-import") (part "TEST-POINT_SMD-SMD-10SN"))
    )
    (comp (ref "TP63")
      (value "TEST-POINT_SMD-SMD-10SN")
      (footprint "eagle-import:TESTPOINT_SMD-10SN")
      (libsource (lib "eagle-import") (part "TEST-POINT_SMD-SMD-10SN"))
    )
    (comp (ref "TP64")
      (value "TEST-POINT_SMD-SMD-10SN")
      (footprint "eagle-import:TESTPOINT_SMD-10SN")
      (libsource (lib "eagle-import") (part "TEST-POINT_SMD-SMD-10SN"))
    )
    (comp (ref "TP67")
      (value "TEST-POINT_SMD-SMD-10SN")
      (footprint "eagle-import:TESTPOINT_SMD-10SN")
      (libsource (lib "eagle-import") (part "TEST-POINT_SMD-SMD-10SN"))
    )
    (comp (ref "TP68")
      (value "TEST-POINT_SMD-SMD-10SN")
      (footprint "eagle-import:TESTPOINT_SMD-10SN")
      (libsource (lib "eagle-import") (part "TEST-POINT_SMD-SMD-10SN"))
    )
    (comp (ref "U8")
      (value "LP2985AIM5-3.3_NOPB")
      (footprint "eagle-import:SOT-23")
      (fields
        (field (name "MANUFACTURER_PART_NUMBER") "LP2985AIM5-3.3/NOPB")
        (field (name "MOUSER_PART_NUMBER") "926-2985AIM53.3/NOPB")
        (field (name "RS_PART_NUMBER") "6520033P")
      )
      (libsource (lib "eagle-import") (part "LP2985AIM5-3.3_NOPB"))
    )
    (comp (ref "U12")
      (value "MIC842LYC5")
      (footprint "eagle-import:SC70-5")
      (libsource (lib "eagle-import") (part "MIC842LYC5"))
    )
    (comp (ref "U13")
      (value "MIC842LYC5")
      (footprint "eagle-import:SC70-5")
      (libsource (lib "eagle-import") (part "MIC842LYC5"))
    )
    (comp (ref "U14")
      (value "MAX4211FETE")
      (footprint "eagle-import:QFN65P400X400X80-17T210")
      (fields (field (name "MPN") "MAX4211FETE+"))
      (libsource (lib "eagle-import") (part "MAX4211"))
    )
    (comp (ref "U16")
      (value "MAX7310ATE")
      (footprint "eagle-import:QFN65P400X400X80-17T210")
      (fields
        (field (name "MPN") "MAX7310ATE+")
        (field (name "MFR") "Maxim")
        (field (name "MPN_1") "MAX7310ATE")
      )
      (libsource (lib "eagle-import") (part "MAX7310"))
    )
    (comp (ref "J2")
      (value "J-SAMTEC-TFM-110-X1-XXX-D-RA")
      (footprint "eagle-import:J-SAMTEC-TFM-110-X1-XXX-D-RA")
      (fields (field (name "MFR") "Samtec") (field (name "MPN") "TFM-110-01-L-D-RA "))
      (libsource (lib "eagle-import") (part "J-SAMTEC-TFM-110-X1-XXX-D-RA"))
    )
    (comp (ref "J4")
      (value "TFM-120-01-L-D-RA")
      (footprint "eagle-import:J-SAMTEC-TFM-120-X1-XXX-D-RA")
      (libsource (lib "eagle-import") (part "J-SAMTEC-TFM-120-X1-XXX-D-RA"))
    )
    (comp (ref "PCB1")
      (value "ORESAT-CARD-V1.3-CFC")
      (footprint "eagle-import:ORESAT-CARD-V1.3-CFC")
      (libsource (lib "eagle-import") (part "ORESAT-CARD-V1.3-CFC"))
    )
    (comp (ref "U$1")
      (value "FLIGHMARKERNEW")
      (footprint "eagle-import:FLIGHTMARKER_NEW_BOARDS")
      (libsource (lib "eagle-import") (part "FLIGHMARKERNEW"))
    )
    (comp (ref "C11")
      (value "0.1u")
      (footprint "eagle-import:.0603-B")
      (libsource (lib "eagle-import") (part "C-EU0603-B"))
    )
    (comp (ref "C21")
      (value "NP")
      (footprint "eagle-import:.0603-B")
      (libsource (lib "eagle-import") (part "C-EU0603-B"))
    )
    (comp (ref "C100")
      (value "0.1u")
      (footprint "eagle-import:.0603-B")
      (libsource (lib "eagle-import") (part "C-EU0603-B"))
    )
    (comp (ref "C101")
      (value "0.1u")
      (footprint "eagle-import:.0603-B")
      (libsource (lib "eagle-import") (part "C-EU0603-B"))
    )
    (comp (ref "C102")
      (value "0.1u")
      (footprint "eagle-import:.0603-B")
      (libsource (lib "eagle-import") (part "C-EU0603-B"))
    )
    (comp (ref "C103")
      (value "0.1u")
      (footprint "eagle-import:.0603-B")
      (libsource (lib "eagle-import") (part "C-EU0603-B"))
    )
    (comp (ref "C104")
      (value "0.1u")
      (footprint "eagle-import:.0603-B")
      (libsource (lib "eagle-import") (part "C-EU0603-B"))
    )
    (comp (ref "D2")
      (value "GREEN")
      (footprint "eagle-import:LED-0603")
      (description "Green 573nm LED Indication - Discrete 2V 0603 (1608 Metric)")
      (fields
        (field (name "DIGI-KEY_PART_NUMBER") "732-12017-1-ND")
        (field (name "MANUFACTURER") "Würth Elektronik")
      )
      (libsource (lib "eagle-import") (part "LED-GREEN0603"))
    )
    (comp (ref "Q7")
      (value "MOSFET-PCH-SOT23-6")
      (footprint "eagle-import:SOT23-6")
      (fields (field (name "MPN") "DMP3050LVT-7") (field (name "MPN_1") "DMP3050LVT-7"))
      (libsource (lib "eagle-import") (part "MOSFET-PCH-SOT23-6"))
    )
    (comp (ref "Q8")
      (value "PMV45EN")
      (footprint "eagle-import:SOT23")
      (fields (field (name "MPN") "PMV45EN2R"))
      (libsource (lib "eagle-import") (part "PMV45EN"))
    )
    (comp (ref "R9")
      (value "10k")
      (footprint "eagle-import:.0603-B")
      (libsource (lib "eagle-import") (part "R-US_0603-B"))
    )
    (comp (ref "R10")
      (value "10k")
      (footprint "eagle-import:.0603-B")
      (libsource (lib "eagle-import") (part "R-US_0603-B"))
    )
    (comp (ref "R11")
      (value "1k")
      (footprint "eagle-import:.0603-B")
      (libsource (lib "eagle-import") (part "R-US_0603-B"))
    )
    (comp (ref "R12")
      (value "NP")
      (footprint "eagle-import:.0402-C-NOSILK")
      (fields (field (name "MFR") "Yageo") (field (name "MPN") "RC0201FR-07100RL"))
      (libsource (lib "eagle-import") (part "R-US_0402-C-NOSILK"))
    )
    (comp (ref "R13")
      (value "NP")
      (footprint "eagle-import:.0402-C-NOSILK")
      (fields (field (name "MFR") "Yageo") (field (name "MPN") "RC0201FR-07100RL"))
      (libsource (lib "eagle-import") (part "R-US_0402-C-NOSILK"))
    )
    (comp (ref "R14")
      (value "NP")
      (footprint "eagle-import:.0402-C-NOSILK")
      (fields (field (name "MFR") "Yageo") (field (name "MPN") "RC0201FR-07100RL"))
      (libsource (lib "eagle-import") (part "R-US_0402-C-NOSILK"))
    )
    (comp (ref "R15")
      (value "0")
      (footprint "eagle-import:.0603-B")
      (libsource (lib "eagle-import") (part "R-US_0603-B"))
    )
    (comp (ref "R27")
      (value "100")
      (footprint "eagle-import:.0402-A")
      (fields (field (name "MFR") "Vishay") (field (name "MPN") "RCA0402100RFKEDHP"))
      (libsource (lib "eagle-import") (part "R-US_0402-A"))
    )
    (comp (ref "TP40")
      (value "TEST-POINT_SMD-SMD-10SN")
      (footprint "eagle-import:TESTPOINT_SMD-10SN")
      (libsource (lib "eagle-import") (part "TEST-POINT_SMD-SMD-10SN"))
    )
    (comp (ref "U1")
      (value "PIRT1280A1-12")
      (footprint "eagle-import:PIRT1280A1-12")
      (libsource (lib "eagle-import") (part "PIRT1280A1-12"))
    )
    (comp (ref "X1")
      (value "16MHz")
      (footprint "eagle-import:OSC_2.5X2.0")
      (fields (field (name "MPN") "ISM95-3251AH-16.000MHZ"))
      (libsource (lib "eagle-import") (part "OSC_GENERIC_2.5X2.0"))
    )
  )
  (nets
    (net (code "1") (name "3.3V") (class "Default")
      (node (ref "C11") (pin "1") (pinfunction "1_1") (pintype "passive"))
      (node (ref "C19") (pin "1") (pinfunction "1_1") (pintype "passive"))
      (node (ref "C40") (pin "1") (pinfunction "1_1") (pintype "passive"))
      (node (ref "R2") (pin "16") (pinfunction "16_16") (pintype "passive"))
      (node (ref "U7") (pin "3") (pinfunction "VCC_3") (pintype "power_in"))
      (node (ref "U8") (pin "5") (pinfunction "VOUT_5") (pintype "power_in"))
      (node (ref "X1") (pin "4") (pinfunction "VCC_4") (pintype "power_in"))
    )
    (net (code "2") (name "AD0") (class "Default")
      (node (ref "R57") (pin "1") (pinfunction "1_1") (pintype "passive"))
      (node (ref "R58") (pin "2") (pinfunction "2_2") (pintype "passive"))
      (node (ref "R69") (pin "2") (pinfunction "2_2") (pintype "passive"))
      (node (ref "R70") (pin "1") (pinfunction "1_1") (pintype "passive"))
      (node (ref "U16") (pin "1") (pinfunction "AD0_1") (pintype "input"))
    )
    (net (code "3") (name "AD1") (class "Default")
      (node (ref "R55") (pin "1") (pinfunction "1_1") (pintype "passive"))
      (node (ref "R56") (pin "2") (pinfunction "2_2") (pintype "passive"))
      (node (ref "R67") (pin "2") (pinfunction "2_2") (pintype "passive"))
      (node (ref "R68") (pin "1") (pinfunction "1_1") (pintype "passive"))
      (node (ref "U16") (pin "2") (pinfunction "AD1_2") (pintype "input"))
    )
    (net (code "4") (name "AD2") (class "Default")
      (node (ref "R53") (pin "1") (pinfunction "1_1") (pintype "passive"))
      (node (ref "R54") (pin "2") (pinfunction "2_2") (pintype "passive"))
      (node (ref "R65") (pin "2") (pinfunction "2_2") (pintype "passive"))
      (node (ref "R66") (pin "1") (pinfunction "1_1") (pintype "passive"))
      (node (ref "U16") (pin "3") (pinfunction "AD2_3") (pintype "input"))
    )
    (net (code "5") (name "BOOT0") (class "Default")
      (node (ref "TP51") (pin "TP") (pinfunction "1_TP") (pintype "passive"))
      (node (ref "U16") (pin "10") (pinfunction "IO5_10") (pintype "bidirectional"))
    )
    (net (code "6") (name "CB-RESET") (class "Default")
      (node (ref "R39") (pin "2") (pinfunction "2_2") (pintype "passive"))
      (node (ref "TP54") (pin "TP") (pinfunction "1_TP") (pintype "passive"))
      (node (ref "U14") (pin "9") (pinfunction "CIN2-_9") (pintype "input"))
      (node (ref "U16") (pin "9") (pinfunction "IO4_9") (pintype "bidirectional"))
    )
    (net (code "7") (name "CB_CTRL") (class "Default")
      (node (ref "Q2") (pin "1") (pinfunction "G_1") (pintype "passive"))
      (node (ref "Q5") (pin "3") (pinfunction "G_3") (pintype "passive"))
      (node (ref "R64") (pin "1") (pinfunction "1_1") (pintype "passive"))
      (node (ref "TP52") (pin "TP") (pinfunction "1_TP") (pintype "passive"))
      (node (ref "U14") (pin "3") (pinfunction "LE_3") (pintype "input"))
      (node (ref "U14") (pin "4") (pinfunction "COUT1_4") (pintype "open_collector"))
      (node (ref "U14") (pin "6") (pinfunction "COUT2_6") (pintype "open_collector"))
    )
    (net (code "8") (name "GND") (class "Default")
      (node (ref "C1") (pin "2") (pinfunction "2_2") (pintype "passive"))
      (node (ref "C10") (pin "2") (pinfunction "2_2") (pintype "passive"))
      (node (ref "C100") (pin "2") (pinfunction "2_2") (pintype "passive"))
      (node (ref "C101") (pin "2") (pinfunction "2_2") (pintype "passive"))
      (node (ref "C102") (pin "2") (pinfunction "2_2") (pintype "passive"))
      (node (ref "C103") (pin "2") (pinfunction "2_2") (pintype "passive"))
      (node (ref "C104") (pin "2") (pinfunction "2_2") (pintype "passive"))
      (node (ref "C11") (pin "2") (pinfunction "2_2") (pintype "passive"))
      (node (ref "C12") (pin "2") (pinfunction "2_2") (pintype "passive"))
      (node (ref "C13") (pin "2") (pinfunction "2_2") (pintype "passive"))
      (node (ref "C14") (pin "2") (pinfunction "2_2") (pintype "passive"))
      (node (ref "C15") (pin "2") (pinfunction "2_2") (pintype "passive"))
      (node (ref "C16") (pin "2") (pinfunction "2_2") (pintype "passive"))
      (node (ref "C17") (pin "2") (pinfunction "2_2") (pintype "passive"))
      (node (ref "C18") (pin "2") (pinfunction "2_2") (pintype "passive"))
      (node (ref "C19") (pin "2") (pinfunction "2_2") (pintype "passive"))
      (node (ref "C2") (pin "2") (pinfunction "2_2") (pintype "passive"))
      (node (ref "C20") (pin "2") (pinfunction "2_2") (pintype "passive"))
      (node (ref "C3") (pin "2") (pinfunction "2_2") (pintype "passive"))
      (node (ref "C32") (pin "2") (pinfunction "2_2") (pintype "passive"))
      (node (ref "C34") (pin "2") (pinfunction "2_2") (pintype "passive"))
      (node (ref "C35") (pin "2") (pinfunction "2_2") (pintype "passive"))
      (node (ref "C39") (pin "1") (pinfunction "1_1") (pintype "passive"))
      (node (ref "C4") (pin "2") (pinfunction "2_2") (pintype "passive"))
      (node (ref "C40") (pin "2") (pinfunction "2_2") (pintype "passive"))
      (node (ref "C44") (pin "2") (pinfunction "2_2") (pintype "passive"))
      (node (ref "C5") (pin "2") (pinfunction "2_2") (pintype "passive"))
      (node (ref "C6") (pin "2") (pinfunction "2_2") (pintype "passive"))
      (node (ref "C7") (pin "2") (pinfunction "2_2") (pintype "passive"))
      (node (ref "C8") (pin "2") (pinfunction "2_2") (pintype "passive"))
      (node (ref "C9") (pin "2") (pinfunction "2_2") (pintype "passive"))
      (node (ref "D1") (pin "C") (pinfunction "C_C") (pintype "passive"))
      (node (ref "D2") (pin "C") (pinfunction "C_C") (pintype "passive"))
      (node (ref "D6") (pin "C") (pinfunction "C_C") (pintype "passive"))
      (node (ref "D7") (pin "C") (pinfunction "C_C") (pintype "passive"))
      (node (ref "J4") (pin "27") (pinfunction "27_27") (pintype "passive"))
      (node (ref "J4") (pin "28") (pinfunction "28_28") (pintype "passive"))
      (node (ref "J4") (pin "29") (pinfunction "29_29") (pintype "passive"))
      (node (ref "J4") (pin "30") (pinfunction "30_30") (pintype "passive"))
      (node (ref "J4") (pin "31") (pinfunction "31_31") (pintype "passive"))
      (node (ref "J4") (pin "32") (pinfunction "32_32") (pintype "passive"))
      (node (ref "J4") (pin "37") (pinfunction "37_37") (pintype "passive"))
      (node (ref "J4") (pin "38") (pinfunction "38_38") (pintype "passive"))
      (node (ref "Q2") (pin "2") (pinfunction "S_2") (pintype "passive"))
      (node (ref "Q4") (pin "2") (pinfunction "S_2") (pintype "passive"))
      (node (ref "Q8") (pin "2") (pinfunction "S_2") (pintype "passive"))
      (node (ref "R10") (pin "1") (pinfunction "1_1") (pintype "passive"))
      (node (ref "R18") (pin "1") (pinfunction "1_1") (pintype "passive"))
      (node (ref "R2") (pin "10") (pinfunction "10_10") (pintype "passive"))
      (node (ref "R20") (pin "10") (pinfunction "55_10") (pintype "passive"))
      (node (ref "R20") (pin "5") (pinfunction "55_5") (pintype "passive"))
      (node (ref "R3") (pin "1") (pinfunction "1_1") (pintype "passive"))
      (node (ref "R33") (pin "1") (pinfunction "1_1") (pintype "passive"))
      (node (ref "R39") (pin "1") (pinfunction "1_1") (pintype "passive"))
      (node (ref "R4") (pin "1") (pinfunction "1_1") (pintype "passive"))
      (node (ref "R42") (pin "1") (pinfunction "1_1") (pintype "passive"))
      (node (ref "R46") (pin "1") (pinfunction "1_1") (pintype "passive"))
      (node (ref "R5") (pin "1") (pinfunction "1_1") (pintype "passive"))
      (node (ref "R51") (pin "1") (pinfunction "1_1") (pintype "passive"))
      (node (ref "R54") (pin "1") (pinfunction "1_1") (pintype "passive"))
      (node (ref "R56") (pin "1") (pinfunction "1_1") (pintype "passive"))
      (node (ref "R58") (pin "1") (pinfunction "1_1") (pintype "passive"))
      (node (ref "R6") (pin "1") (pinfunction "1_1") (pintype "passive"))
      (node (ref "R7") (pin "1") (pinfunction "1_1") (pintype "passive"))
      (node (ref "U1") (pin "17") (pinfunction "VN_17") (pintype "power_in"))
      (node (ref "U1") (pin "22") (pinfunction "TEC-_22") (pintype "passive"))
      (node (ref "U1") (pin "29") (pinfunction "VGND_29") (pintype "power_in"))
      (node (ref "U1") (pin "44") (pinfunction "THERM-_44") (pintype "passive"))
      (node (ref "U1") (pin "6") (pinfunction "VNOUT_6") (pintype "power_in"))
      (node (ref "U12") (pin "2") (pinfunction "GND_2") (pintype "power_in"))
      (node (ref "U13") (pin "2") (pinfunction "GND_2") (pintype "power_in"))
      (node (ref "U14") (pin "7") (pinfunction "GND_7") (pintype "power_in"))
      (node (ref "U14") (pin "EPAD") (pinfunction "GND_EPAD") (pintype "power_in"))
      (node (ref "U16") (pin "6") (pinfunction "GND_6") (pintype "power_in"))
      (node (ref "U16") (pin "EPAD") (pinfunction "GND_EPAD") (pintype "power_in"))
      (node (ref "U2") (pin "11") (pinfunction "GND_11") (pintype "power_in"))
      (node (ref "U2") (pin "5") (pinfunction "ILIM_5") (pintype "passive"))
      (node (ref "U2") (pin "8") (pinfunction "GND_8") (pintype "power_in"))
      (node (ref "U3") (pin "11") (pinfunction "GND_11") (pintype "power_in"))
      (node (ref "U3") (pin "5") (pinfunction "ILIM_5") (pintype "passive"))
      (node (ref "U3") (pin "8") (pinfunction "GND_8") (pintype "power_in"))
      (node (ref "U4") (pin "11") (pinfunction "GND_11") (pintype "power_in"))
      (node (ref "U4") (pin "5") (pinfunction "ILIM_5") (pintype "passive"))
      (node (ref "U4") (pin "8") (pinfunction "GND_8") (pintype "power_in"))
      (node (ref "U5") (pin "11") (pinfunction "GND_11") (pintype "power_in"))
      (node (ref "U5") (pin "5") (pinfunction "ILIM_5") (pintype "passive"))
      (node (ref "U5") (pin "8") (pinfunction "GND_8") (pintype "power_in"))
      (node (ref "U6") (pin "11") (pinfunction "GND_11") (pintype "power_in"))
      (node (ref "U6") (pin "5") (pinfunction "ILIM_5") (pintype "passive"))
      (node (ref "U6") (pin "8") (pinfunction "GND_8") (pintype "power_in"))
      (node (ref "U7") (pin "12") (pinfunction "GND_12") (pintype "power_in"))
      (node (ref "U8") (pin "2") (pinfunction "GND_2") (pintype "power_in"))
      (node (ref "X1") (pin "2") (pinfunction "GND_2") (pintype "power_in"))
    )
    (net (code "9") (name "Net-(C33-Pad1)") (class "Default")
      (node (ref "C33") (pin "1") (pinfunction "1_1") (pintype "passive"))
      (node (ref "R33") (pin "2") (pinfunction "2_2") (pintype "passive"))
      (node (ref "R38") (pin "2") (pinfunction "2_2") (pintype "passive"))
    )
    (net (code "10") (name "Net-(D1-PadA)") (class "Default")
      (node (ref "D1") (pin "A") (pinfunction "A_A") (pintype "passive"))
      (node (ref "R1") (pin "1") (pinfunction "1_1") (pintype "passive"))
    )
    (net (code "11") (name "Net-(D2-PadA)") (class "Default")
      (node (ref "D2") (pin "A") (pinfunction "A_A") (pintype "passive"))
      (node (ref "R11") (pin "1") (pinfunction "1_1") (pintype "passive"))
    )
    (net (code "12") (name "Net-(D6-PadA)") (class "Default")
      (node (ref "D6") (pin "A") (pinfunction "A_A") (pintype "passive"))
      (node (ref "R49") (pin "1") (pinfunction "1_1") (pintype "passive"))
    )
    (net (code "13") (name "Net-(D7-PadA)") (class "Default")
      (node (ref "D7") (pin "A") (pinfunction "A_A") (pintype "passive"))
      (node (ref "R61") (pin "1") (pinfunction "1_1") (pintype "passive"))
    )
    (net (code "14") (name "Net-(Q3A-G)") (class "Default")
      (node (ref "Q3") (pin "1") (pinfunction "G_1") (pintype "passive"))
      (node (ref "R35") (pin "2") (pinfunction "2_2") (pintype "passive"))
    )
    (net (code "15") (name "Net-(Q3A-S)") (class "Default")
      (node (ref "Q3") (pin "5") (pinfunction "S_5") (pintype "passive"))
      (node (ref "R48") (pin "2") (pinfunction "2_2") (pintype "passive"))
    )
    (net (code "16") (name "Net-(Q3B-G)") (class "Default")
      (node (ref "Q3") (pin "3") (pinfunction "G_3") (pintype "passive"))
      (node (ref "R43") (pin "2") (pinfunction "2_2") (pintype "passive"))
    )
    (net (code "17") (name "Net-(Q3B-S)") (class "Default")
      (node (ref "Q3") (pin "2") (pinfunction "S_2") (pintype "passive"))
      (node (ref "R41") (pin "2") (pinfunction "2_2") (pintype "passive"))
    )
    (net (code "18") (name "Net-(Q4-D)") (class "Default")
      (node (ref "Q4") (pin "3") (pinfunction "D_3") (pintype "passive"))
      (node (ref "Q6") (pin "3") (pinfunction "G_3") (pintype "passive"))
      (node (ref "R52") (pin "1") (pinfunction "1_1") (pintype "passive"))
    )
    (net (code "19") (name "Net-(Q5-S)") (class "Default")
      (node (ref "Q5") (pin "4") (pinfunction "S_4") (pintype "passive"))
      (node (ref "R63") (pin "2") (pinfunction "2_2") (pintype "passive"))
      (node (ref "R64") (pin "2") (pinfunction "2_2") (pintype "passive"))
      (node (ref "U14") (pin "15") (pinfunction "RS-_15") (pintype "passive"))
    )
    (net (code "20") (name "Net-(Q7-G)") (class "Default")
      (node (ref "C21") (pin "2") (pinfunction "2_2") (pintype "passive"))
      (node (ref "Q7") (pin "3") (pinfunction "G_3") (pintype "passive"))
      (node (ref "R15") (pin "2") (pinfunction "2_2") (pintype "passive"))
      (node (ref "R9") (pin "1") (pinfunction "1_1") (pintype "passive"))
    )
    (net (code "21") (name "Net-(Q8-D)") (class "Default")
      (node (ref "Q8") (pin "3") (pinfunction "D_3") (pintype "passive"))
      (node (ref "R15") (pin "1") (pinfunction "1_1") (pintype "passive"))
    )
    (net (code "22") (name "Net-(R2-Pad1)") (class "Default")
      (node (ref "R2") (pin "1") (pinfunction "1_1") (pintype "passive"))
      (node (ref "R2") (pin "2") (pinfunction "2_2") (pintype "passive"))
    )
    (net (code "23") (name "Net-(R2-Pad6)") (class "Default")
      (node (ref "R2") (pin "6") (pinfunction "6_6") (pintype "passive"))
      (node (ref "R2") (pin "7") (pinfunction "7_7") (pintype "passive"))
    )
    (net (code "24") (name "Net-(R19-Pad1)") (class "Default")
      (node (ref "R19") (pin "1") (pinfunction "1_1") (pintype "passive"))
      (node (ref "R8") (pin "2") (pinfunction "2_2") (pintype "passive"))
    )
    (net (code "25") (name "Net-(R20-44)") (class "Default")
      (node (ref "R20") (pin "4") (pinfunction "44_4") (pintype "passive"))
      (node (ref "TP18") (pin "1") (pinfunction "1_1") (pintype "passive"))
      (node (ref "U2") (pin "3") (pinfunction "EN/UV_3") (pintype "input"))
      (node (ref "U4") (pin "3") (pinfunction "EN/UV_3") (pintype "input"))
      (node (ref "U7") (pin "2") (pinfunction "OUT2_2") (pintype "output"))
    )
    (net (code "26") (name "Net-(R20-66)") (class "Default")
      (node (ref "R1") (pin "2") (pinfunction "2_2") (pintype "passive"))
      (node (ref "R20") (pin "6") (pinfunction "66_6") (pintype "passive"))
      (node (ref "TP16") (pin "1") (pinfunction "1_1") (pintype "passive"))
      (node (ref "U5") (pin "3") (pinfunction "EN/UV_3") (pintype "input"))
      (node (ref "U6") (pin "3") (pinfunction "EN/UV_3") (pintype "input"))
      (node (ref "U7") (pin "1") (pinfunction "OUT1_1") (pintype "output"))
    )
    (net (code "27") (name "Net-(R20-77)") (class "Default")
      (node (ref "R20") (pin "7") (pinfunction "77_7") (pintype "passive"))
      (node (ref "TP1") (pin "1") (pinfunction "1_1") (pintype "passive"))
      (node (ref "U3") (pin "3") (pinfunction "EN/UV_3") (pintype "input"))
      (node (ref "U7") (pin "14") (pinfunction "OUT3_14") (pintype "output"))
    )
    (net (code "28") (name "Net-(TP2-1)") (class "Default")
      (node (ref "TP2") (pin "TP") (pinfunction "1_TP") (pintype "passive"))
      (node (ref "U3") (pin "4") (pinfunction "PG_4") (pintype "open_collector"))
    )
    (net (code "29") (name "Net-(TP5-1)") (class "Default")
      (node (ref "TP5") (pin "TP") (pinfunction "1_TP") (pintype "passive"))
      (node (ref "U2") (pin "4") (pinfunction "PG_4") (pintype "open_collector"))
    )
    (net (code "30") (name "Net-(TP8-1)") (class "Default")
      (node (ref "TP8") (pin "TP") (pinfunction "1_TP") (pintype "passive"))
      (node (ref "U4") (pin "4") (pinfunction "PG_4") (pintype "open_collector"))
    )
    (net (code "31") (name "Net-(TP11-1)") (class "Default")
      (node (ref "TP11") (pin "TP") (pinfunction "1_TP") (pintype "passive"))
      (node (ref "U5") (pin "4") (pinfunction "PG_4") (pintype "open_collector"))
    )
    (net (code "32") (name "Net-(TP14-1)") (class "Default")
      (node (ref "TP14") (pin "TP") (pinfunction "1_TP") (pintype "passive"))
      (node (ref "U6") (pin "4") (pinfunction "PG_4") (pintype "open_collector"))
    )
    (net (code "33") (name "Net-(TP40-1)") (class "Default")
      (node (ref "TP40") (pin "TP") (pinfunction "1_TP") (pintype "passive"))
      (node (ref "U1") (pin "21") (pinfunction "JAMSYNC_21") (pintype "input"))
    )
    (net (code "34") (name "Net-(TP43-1)") (class "Default")
      (node (ref "R43") (pin "1") (pinfunction "1_1") (pintype "passive"))
      (node (ref "TP43") (pin "TP") (pinfunction "1_TP") (pintype "passive"))
      (node (ref "U13") (pin "4") (pinfunction "OUT_4") (pintype "output"))
    )
    (net (code "35") (name "Net-(TP44-1)") (class "Default")
      (node (ref "R35") (pin "1") (pinfunction "1_1") (pintype "passive"))
      (node (ref "TP44") (pin "TP") (pinfunction "1_TP") (pintype "passive"))
      (node (ref "U12") (pin "4") (pinfunction "OUT_4") (pintype "output"))
    )
    (net (code "36") (name "Net-(TP47-1)") (class "Default")
      (node (ref "R42") (pin "2") (pinfunction "2_2") (pintype "passive"))
      (node (ref "R47") (pin "1") (pinfunction "1_1") (pintype "passive"))
      (node (ref "TP47") (pin "TP") (pinfunction "1_TP") (pintype "passive"))
      (node (ref "U14") (pin "11") (pinfunction "CIN1-_11") (pintype "input"))
    )
    (net (code "37") (name "Net-(TP53-1)") (class "Default")
      (node (ref "TP53") (pin "TP") (pinfunction "1_TP") (pintype "passive"))
      (node (ref "U16") (pin "11") (pinfunction "IO6_11") (pintype "bidirectional"))
    )
    (net (code "38") (name "Net-(TP56-1)") (class "Default")
      (node (ref "TP56") (pin "TP") (pinfunction "1_TP") (pintype "passive"))
      (node (ref "U16") (pin "12") (pinfunction "IO7_12") (pintype "bidirectional"))
    )
    (net (code "39") (name "Net-(TP57-1)") (class "Default")
      (node (ref "R50") (pin "1") (pinfunction "1_1") (pintype "passive"))
      (node (ref "R51") (pin "2") (pinfunction "2_2") (pintype "passive"))
      (node (ref "TP57") (pin "TP") (pinfunction "1_TP") (pintype "passive"))
      (node (ref "U14") (pin "10") (pinfunction "CIN1+_10") (pintype "input"))
    )
    (net (code "40") (name "Net-(U1A-OUT2N)") (class "Default")
      (node (ref "R12") (pin "1") (pinfunction "1_1") (pintype "passive"))
      (node (ref "U1") (pin "12") (pinfunction "OUT2N_12") (pintype "output"))
    )
    (net (code "41") (name "Net-(U1A-OUT2P)") (class "Default")
      (node (ref "R12") (pin "2") (pinfunction "2_2") (pintype "passive"))
      (node (ref "U1") (pin "11") (pinfunction "OUT2P_11") (pintype "output"))
    )
    (net (code "42") (name "Net-(U1A-OUT3N)") (class "Default")
      (node (ref "R13") (pin "1") (pinfunction "1_1") (pintype "passive"))
      (node (ref "U1") (pin "10") (pinfunction "OUT3N_10") (pintype "output"))
    )
    (net (code "43") (name "Net-(U1A-OUT3P)") (class "Default")
      (node (ref "R13") (pin "2") (pinfunction "2_2") (pintype "passive"))
      (node (ref "U1") (pin "9") (pinfunction "OUT3P_9") (pintype "output"))
    )
    (net (code "44") (name "Net-(U1A-OUT4N)") (class "Default")
      (node (ref "R14") (pin "1") (pinfunction "1_1") (pintype "passive"))
      (node (ref "U1") (pin "8") (pinfunction "OUT4N_8") (pintype "output"))
    )
    (net (code "45") (name "Net-(U1A-OUT4P)") (class "Default")
      (node (ref "R14") (pin "2") (pinfunction "2_2") (pintype "passive"))
      (node (ref "U1") (pin "7") (pinfunction "OUT4P_7") (pintype "output"))
    )
    (net (code "46") (name "Net-(U1A-REFCLK)") (class "Default")
      (node (ref "R27") (pin "2") (pinfunction "2_2") (pintype "passive"))
      (node (ref "U1") (pin "20") (pinfunction "REFCLK_20") (pintype "input"))
    )
    (net (code "47") (name "Net-(U1A-TEC+)") (class "Default")
      (node (ref "Q7") (pin "1") (pinfunction "D_1") (pintype "passive"))
      (node (ref "Q7") (pin "2") (pinfunction "D_2") (pintype "passive"))
      (node (ref "Q7") (pin "5") (pinfunction "D_5") (pintype "passive"))
      (node (ref "Q7") (pin "6") (pinfunction "D_6") (pintype "passive"))
      (node (ref "R11") (pin "2") (pinfunction "2_2") (pintype "passive"))
      (node (ref "U1") (pin "23") (pinfunction "TEC+_23") (pintype "passive"))
    )
    (net (code "48") (name "Net-(U2-SET)") (class "Default")
      (node (ref "C13") (pin "1") (pinfunction "1_1") (pintype "passive"))
      (node (ref "R4") (pin "2") (pinfunction "2_2") (pintype "passive"))
      (node (ref "U2") (pin "7") (pinfunction "SET_7") (pintype "input"))
    )
    (net (code "49") (name "Net-(U3-SET)") (class "Default")
      (node (ref "C12") (pin "1") (pinfunction "1_1") (pintype "passive"))
      (node (ref "R3") (pin "2") (pinfunction "2_2") (pintype "passive"))
      (node (ref "U3") (pin "7") (pinfunction "SET_7") (pintype "input"))
    )
    (net (code "50") (name "Net-(U4-SET)") (class "Default")
      (node (ref "C14") (pin "1") (pinfunction "1_1") (pintype "passive"))
      (node (ref "R5") (pin "2") (pinfunction "2_2") (pintype "passive"))
      (node (ref "U4") (pin "7") (pinfunction "SET_7") (pintype "input"))
    )
    (net (code "51") (name "Net-(U5-SET)") (class "Default")
      (node (ref "C15") (pin "1") (pinfunction "1_1") (pintype "passive"))
      (node (ref "R6") (pin "2") (pinfunction "2_2") (pintype "passive"))
      (node (ref "U5") (pin "7") (pinfunction "SET_7") (pintype "input"))
    )
    (net (code "52") (name "Net-(U6-SET)") (class "Default")
      (node (ref "C16") (pin "1") (pinfunction "1_1") (pintype "passive"))
      (node (ref "R7") (pin "2") (pinfunction "2_2") (pintype "passive"))
      (node (ref "U6") (pin "7") (pinfunction "SET_7") (pintype "input"))
    )
    (net (code "53") (name "Net-(U7-1IN+)") (class "Default")
      (node (ref "C17") (pin "1") (pinfunction "1_1") (pintype "passive"))
      (node (ref "R18") (pin "2") (pinfunction "2_2") (pintype "passive"))
      (node (ref "R19") (pin "2") (pinfunction "2_2") (pintype "passive"))
      (node (ref "U7") (pin "11") (pinfunction "4IN+_11") (pintype "input"))
      (node (ref "U7") (pin "5") (pinfunction "2IN+_5") (pintype "input"))
      (node (ref "U7") (pin "7") (pinfunction "1IN+_7") (pintype "input"))
      (node (ref "U7") (pin "9") (pinfunction "3IN+_9") (pintype "input"))
    )
    (net (code "54") (name "Net-(U7-1IN-)") (class "Default")
      (node (ref "R2") (pin "11") (pinfunction "11_11") (pintype "passive"))
      (node (ref "R2") (pin "12") (pinfunction "12_12") (pintype "passive"))
      (node (ref "U7") (pin "6") (pinfunction "1IN-_6") (pintype "input"))
    )
    (net (code "55") (name "Net-(U7-2IN-)") (class "Default")
      (node (ref "R2") (pin "13") (pinfunction "13_13") (pintype "passive"))
      (node (ref "R2") (pin "5") (pinfunction "5_5") (pintype "passive"))
      (node (ref "U7") (pin "4") (pinfunction "2IN-_4") (pintype "input"))
    )
    (net (code "56") (name "Net-(U7-3IN-)") (class "Default")
      (node (ref "R2") (pin "14") (pinfunction "14_14") (pintype "passive"))
      (node (ref "R2") (pin "4") (pinfunction "4_4") (pintype "passive"))
      (node (ref "U7") (pin "8") (pinfunction "3IN-_8") (pintype "input"))
    )
    (net (code "57") (name "Net-(U7-4IN-)") (class "Default")
      (node (ref "R2") (pin "15") (pinfunction "15_15") (pintype "passive"))
      (node (ref "R2") (pin "3") (pinfunction "3_3") (pintype "passive"))
      (node (ref "U7") (pin "10") (pinfunction "4IN-_10") (pintype "input"))
    )
    (net (code "58") (name "Net-(U8-BYPASS)") (class "Default")
      (node (ref "C20") (pin "1") (pinfunction "1_1") (pintype "passive"))
      (node (ref "U8") (pin "4") (pinfunction "BYPASS_4") (pintype "power_in"))
    )
    (net (code "59") (name "Net-(U12-INP)") (class "Default")
      (node (ref "C32") (pin "1") (pinfunction "1_1") (pintype "passive"))
      (node (ref "R36") (pin "1") (pinfunction "1_1") (pintype "passive"))
      (node (ref "R37") (pin "1") (pinfunction "1_1") (pintype "passive"))
      (node (ref "U12") (pin "1") (pinfunction "INP_1") (pintype "input"))
    )
    (net (code "60") (name "Net-(U13-INP)") (class "Default")
      (node (ref "C35") (pin "1") (pinfunction "1_1") (pintype "passive"))
      (node (ref "R44") (pin "1") (pinfunction "1_1") (pintype "passive"))
      (node (ref "R45") (pin "1") (pinfunction "1_1") (pintype "passive"))
      (node (ref "U13") (pin "1") (pinfunction "INP_1") (pintype "input"))
    )
    (net (code "61") (name "Net-(U14-CIN2+)") (class "Default")
      (node (ref "R47") (pin "2") (pinfunction "2_2") (pintype "passive"))
      (node (ref "U14") (pin "12") (pinfunction "REF_12") (pintype "output"))
      (node (ref "U14") (pin "8") (pinfunction "CIN2+_8") (pintype "input"))
    )
    (net (code "62") (name "Net-(U14-INHIBIT)") (class "Default")
      (node (ref "R38") (pin "1") (pinfunction "1_1") (pintype "passive"))
      (node (ref "U14") (pin "5") (pinfunction "INHIBIT_5") (pintype "input"))
    )
    (net (code "63") (name "Net-(U14-IOUT)") (class "Default")
      (node (ref "R50") (pin "2") (pinfunction "2_2") (pintype "passive"))
      (node (ref "U14") (pin "14") (pinfunction "IOUT_14") (pintype "output"))
    )
    (net (code "64") (name "Net-(U14-RS+)") (class "Default")
      (node (ref "C44") (pin "1") (pinfunction "1_1") (pintype "passive"))
      (node (ref "Q6") (pin "1") (pinfunction "D_1") (pintype "passive"))
      (node (ref "Q6") (pin "2") (pinfunction "D_2") (pintype "passive"))
      (node (ref "Q6") (pin "5") (pinfunction "D_5") (pintype "passive"))
      (node (ref "Q6") (pin "6") (pinfunction "D_6") (pintype "passive"))
      (node (ref "R63") (pin "1") (pinfunction "1_1") (pintype "passive"))
      (node (ref "U14") (pin "16") (pinfunction "RS+_16") (pintype "passive"))
    )
    (net (code "65") (name "Net-(U16-~{RESET})") (class "Default")
      (node (ref "R72") (pin "1") (pinfunction "1_1") (pintype "passive"))
      (node (ref "U16") (pin "13") (pinfunction "~{RESET}_13") (pintype "input"))
    )
    (net (code "66") (name "Net-(X1-OUT)") (class "Default")
      (node (ref "R27") (pin "1") (pinfunction "1_1") (pintype "passive"))
      (node (ref "X1") (pin "3") (pinfunction "OUT_3") (pintype "output"))
    )
    (net (code "67") (name "ON{slash}~{OFF}") (class "Default")
      (node (ref "C34") (pin "1") (pinfunction "1_1") (pintype "passive"))
      (node (ref "Q4") (pin "1") (pinfunction "G_1") (pintype "passive"))
      (node (ref "R46") (pin "2") (pinfunction "2_2") (pintype "passive"))
      (node (ref "R49") (pin "2") (pinfunction "2_2") (pintype "passive"))
      (node (ref "TP50") (pin "TP") (pinfunction "1_TP") (pintype "passive"))
      (node (ref "U14") (pin "1") (pinfunction "VCC_1") (pintype "power_in"))
      (node (ref "U16") (pin "8") (pinfunction "IO3_8") (pintype "bidirectional"))
    )
    (net (code "68") (name "OPD_PWR") (class "Default")
      (node (ref "J4") (pin "15") (pinfunction "15_15") (pintype "passive"))
      (node (ref "J4") (pin "16") (pinfunction "16_16") (pintype "passive"))
      (node (ref "R71") (pin "1") (pinfunction "1_1") (pintype "passive"))
    )
    (net (code "69") (name "OPD_SCL") (class "Default")
      (node (ref "J4") (pin "13") (pinfunction "13_13") (pintype "passive"))
      (node (ref "J4") (pin "14") (pinfunction "14_14") (pintype "passive"))
      (node (ref "R48") (pin "1") (pinfunction "1_1") (pintype "passive"))
    )
    (net (code "70") (name "OPD_SDA") (class "Default")
      (node (ref "J4") (pin "11") (pinfunction "11_11") (pintype "passive"))
      (node (ref "J4") (pin "12") (pinfunction "12_12") (pintype "passive"))
      (node (ref "R41") (pin "1") (pinfunction "1_1") (pintype "passive"))
    )
    (net (code "71") (name "OUT1N") (class "Default")
      (node (ref "J2") (pin "5") (pinfunction "5_5") (pintype "passive"))
      (node (ref "J2") (pin "6") (pinfunction "6_6") (pintype "passive"))
      (node (ref "U1") (pin "14") (pinfunction "OUT1N_14") (pintype "output"))
    )
    (net (code "72") (name "OUT1P") (class "Default")
      (node (ref "J2") (pin "7") (pinfunction "7_7") (pintype "passive"))
      (node (ref "J2") (pin "8") (pinfunction "8_8") (pintype "passive"))
      (node (ref "U1") (pin "13") (pinfunction "OUT1P_13") (pintype "output"))
    )
    (net (code "73") (name "PB6{slash}SCL") (class "Default")
      (node (ref "TP67") (pin "TP") (pinfunction "1_TP") (pintype "passive"))
      (node (ref "U16") (pin "4") (pinfunction "IO0_4") (pintype "bidirectional"))
    )
    (net (code "74") (name "PB7{slash}SDA") (class "Default")
      (node (ref "TP68") (pin "TP") (pinfunction "1_TP") (pintype "passive"))
      (node (ref "U16") (pin "5") (pinfunction "IO1_5") (pintype "bidirectional"))
    )
    (net (code "75") (name "PEN-SCL-FILT") (class "Default")
      (node (ref "Q3") (pin "6") (pinfunction "D_6") (pintype "passive"))
      (node (ref "R37") (pin "2") (pinfunction "2_2") (pintype "passive"))
      (node (ref "R65") (pin "1") (pinfunction "1_1") (pintype "passive"))
      (node (ref "R67") (pin "1") (pinfunction "1_1") (pintype "passive"))
      (node (ref "R69") (pin "1") (pinfunction "1_1") (pintype "passive"))
      (node (ref "TP42") (pin "TP") (pinfunction "1_TP") (pintype "passive"))
      (node (ref "U16") (pin "15") (pinfunction "SCL_15") (pintype "input"))
    )
    (net (code "76") (name "PEN-SDA-FILT") (class "Default")
      (node (ref "Q3") (pin "4") (pinfunction "D_4") (pintype "passive"))
      (node (ref "R45") (pin "2") (pinfunction "2_2") (pintype "passive"))
      (node (ref "R66") (pin "2") (pinfunction "2_2") (pintype "passive"))
      (node (ref "R68") (pin "2") (pinfunction "2_2") (pintype "passive"))
      (node (ref "R70") (pin "2") (pinfunction "2_2") (pintype "passive"))
      (node (ref "TP41") (pin "TP") (pinfunction "1_TP") (pintype "passive"))
      (node (ref "U16") (pin "16") (pinfunction "SDA_16") (pintype "bidirectional"))
    )
    (net (code "77") (name "POUT") (class "Default")
      (node (ref "TP64") (pin "TP") (pinfunction "1_TP") (pintype "passive"))
      (node (ref "U14") (pin "13") (pinfunction "POUT_13") (pintype "output"))
    )
    (net (code "78") (name "REFCLK_ENABLE") (class "Default")
      (node (ref "R20") (pin "3") (pinfunction "33_3") (pintype "passive"))
      (node (ref "TP27") (pin "1") (pinfunction "1_1") (pintype "passive"))
      (node (ref "U7") (pin "13") (pinfunction "OUT4_13") (pintype "output"))
      (node (ref "X1") (pin "1") (pinfunction "EN_1") (pintype "passive"))
    )
    (net (code "79") (name "SENSOR_ENABLE") (class "Default")
      (node (ref "J2") (pin "13") (pinfunction "13_13") (pintype "passive"))
      (node (ref "J2") (pin "14") (pinfunction "14_14") (pintype "passive"))
      (node (ref "R8") (pin "1") (pinfunction "1_1") (pintype "passive"))
      (node (ref "TP39") (pin "1") (pinfunction "1_1") (pintype "passive"))
    )
    (net (code "80") (name "SPI_CLK") (class "Default")
      (node (ref "J2") (pin "17") (pinfunction "17_17") (pintype "passive"))
      (node (ref "J2") (pin "18") (pinfunction "18_18") (pintype "passive"))
      (node (ref "U1") (pin "26") (pinfunction "SDCLK_26") (pintype "input"))
    )
    (net (code "81") (name "SPI_MISO") (class "Default")
      (node (ref "J2") (pin "15") (pinfunction "15_15") (pintype "passive"))
      (node (ref "J2") (pin "16") (pinfunction "16_16") (pintype "passive"))
      (node (ref "U1") (pin "27") (pinfunction "SDOUT_27") (pintype "output"))
    )
    (net (code "82") (name "SPI_MOSI") (class "Default")
      (node (ref "J2") (pin "19") (pinfunction "19_19") (pintype "passive"))
      (node (ref "J2") (pin "20") (pinfunction "20_20") (pintype "passive"))
      (node (ref "U1") (pin "25") (pinfunction "SDIN_25") (pintype "input"))
    )
    (net (code "83") (name "TEC_ENABLE") (class "Default")
      (node (ref "J2") (pin "10") (pinfunction "10_10") (pintype "passive"))
      (node (ref "J2") (pin "9") (pinfunction "9_9") (pintype "passive"))
      (node (ref "Q8") (pin "1") (pinfunction "G_1") (pintype "passive"))
      (node (ref "R10") (pin "2") (pinfunction "2_2") (pintype "passive"))
    )
    (net (code "84") (name "THERM+") (class "Default")
      (node (ref "J2") (pin "11") (pinfunction "11_11") (pintype "passive"))
      (node (ref "J2") (pin "12") (pinfunction "12_12") (pintype "passive"))
      (node (ref "U1") (pin "1") (pinfunction "THERM+_1") (pintype "passive"))
    )
    (net (code "85") (name "TXCLKN") (class "Default")
      (node (ref "J2") (pin "1") (pinfunction "1_1") (pintype "passive"))
      (node (ref "J2") (pin "2") (pinfunction "2_2") (pintype "passive"))
      (node (ref "U1") (pin "16") (pinfunction "TXCLKN_16") (pintype "output"))
    )
    (net (code "86") (name "TXCLKP") (class "Default")
      (node (ref "J2") (pin "3") (pinfunction "3_3") (pintype "passive"))
      (node (ref "J2") (pin "4") (pinfunction "4_4") (pintype "passive"))
      (node (ref "U1") (pin "15") (pinfunction "TXCLKP_15") (pintype "output"))
    )
    (net (code "87") (name "VBUS") (class "Default")
      (node (ref "J4") (pin "21") (pinfunction "21_21") (pintype "passive"))
      (node (ref "J4") (pin "22") (pinfunction "22_22") (pintype "passive"))
      (node (ref "J4") (pin "23") (pinfunction "23_23") (pintype "passive"))
      (node (ref "J4") (pin "24") (pinfunction "24_24") (pintype "passive"))
      (node (ref "J4") (pin "25") (pinfunction "25_25") (pintype "passive"))
      (node (ref "J4") (pin "26") (pinfunction "26_26") (pintype "passive"))
      (node (ref "Q6") (pin "4") (pinfunction "S_4") (pintype "passive"))
      (node (ref "R52") (pin "2") (pinfunction "2_2") (pintype "passive"))
    )
    (net (code "88") (name "VBUSP") (class "Default")
      (node (ref "C1") (pin "1") (pinfunction "1_1") (pintype "passive"))
      (node (ref "C18") (pin "1") (pinfunction "1_1") (pintype "passive"))
      (node (ref "C2") (pin "1") (pinfunction "1_1") (pintype "passive"))
      (node (ref "C21") (pin "1") (pinfunction "1_1") (pintype "passive"))
      (node (ref "C3") (pin "1") (pinfunction "1_1") (pintype "passive"))
      (node (ref "C33") (pin "2") (pinfunction "2_2") (pintype "passive"))
      (node (ref "C4") (pin "1") (pinfunction "1_1") (pintype "passive"))
      (node (ref "C5") (pin "1") (pinfunction "1_1") (pintype "passive"))
      (node (ref "Q5") (pin "1") (pinfunction "D_1") (pintype "passive"))
      (node (ref "Q5") (pin "2") (pinfunction "D_2") (pintype "passive"))
      (node (ref "Q5") (pin "5") (pinfunction "D_5") (pintype "passive"))
      (node (ref "Q5") (pin "6") (pinfunction "D_6") (pintype "passive"))
      (node (ref "Q7") (pin "4") (pinfunction "S_4") (pintype "passive"))
      (node (ref "R61") (pin "2") (pinfunction "2_2") (pintype "passive"))
      (node (ref "R9") (pin "2") (pinfunction "2_2") (pintype "passive"))
      (node (ref "TP55") (pin "TP") (pinfunction "1_TP") (pintype "passive"))
      (node (ref "U2") (pin "1") (pinfunction "IN_1") (pintype "power_in"))
      (node (ref "U2") (pin "2") (pinfunction "IN_2") (pintype "power_in"))
      (node (ref "U2") (pin "6") (pinfunction "PGFB_6") (pintype "passive"))
      (node (ref "U3") (pin "1") (pinfunction "IN_1") (pintype "power_in"))
      (node (ref "U3") (pin "2") (pinfunction "IN_2") (pintype "power_in"))
      (node (ref "U3") (pin "6") (pinfunction "PGFB_6") (pintype "passive"))
      (node (ref "U4") (pin "1") (pinfunction "IN_1") (pintype "power_in"))
      (node (ref "U4") (pin "2") (pinfunction "IN_2") (pintype "power_in"))
      (node (ref "U4") (pin "6") (pinfunction "PGFB_6") (pintype "passive"))
      (node (ref "U5") (pin "1") (pinfunction "IN_1") (pintype "power_in"))
      (node (ref "U5") (pin "2") (pinfunction "IN_2") (pintype "power_in"))
      (node (ref "U5") (pin "6") (pinfunction "PGFB_6") (pintype "passive"))
      (node (ref "U6") (pin "1") (pinfunction "IN_1") (pintype "power_in"))
      (node (ref "U6") (pin "2") (pinfunction "IN_2") (pintype "power_in"))
      (node (ref "U6") (pin "6") (pinfunction "PGFB_6") (pintype "passive"))
      (node (ref "U8") (pin "1") (pinfunction "VIN_1") (pintype "power_in"))
      (node (ref "U8") (pin "3") (pinfunction "EN_3") (pintype "input"))
    )
    (net (code "89") (name "VDETCOM-2.9V") (class "Default")
      (node (ref "C102") (pin "1") (pinfunction "1_1") (pintype "passive"))
      (node (ref "C6") (pin "1") (pinfunction "1_1") (pintype "passive"))
      (node (ref "TP22") (pin "TP") (pinfunction "1_TP") (pintype "passive"))
      (node (ref "U1") (pin "31") (pinfunction "VDETCOM~{2.9V}_31") (pintype "power_in"))
      (node (ref "U3") (pin "10") (pinfunction "OUT_10") (pintype "power_in"))
      (node (ref "U3") (pin "9") (pinfunction "OUTS_9") (pintype "power_in"))
    )
    (net (code "90") (name "VPD") (class "Default")
      (node (ref "C39") (pin "2") (pinfunction "2_2") (pintype "passive"))
      (node (ref "R32") (pin "2") (pinfunction "2_2") (pintype "passive"))
      (node (ref "R36") (pin "2") (pinfunction "2_2") (pintype "passive"))
      (node (ref "R44") (pin "2") (pinfunction "2_2") (pintype "passive"))
      (node (ref "R53") (pin "2") (pinfunction "2_2") (pintype "passive"))
      (node (ref "R55") (pin "2") (pinfunction "2_2") (pintype "passive"))
      (node (ref "R57") (pin "2") (pinfunction "2_2") (pintype "passive"))
      (node (ref "R71") (pin "2") (pinfunction "2_2") (pintype "passive"))
      (node (ref "R72") (pin "2") (pinfunction "2_2") (pintype "passive"))
      (node (ref "TP63") (pin "TP") (pinfunction "1_TP") (pintype "passive"))
      (node (ref "U12") (pin "5") (pinfunction "VDD_5") (pintype "power_in"))
      (node (ref "U13") (pin "5") (pinfunction "VDD_5") (pintype "power_in"))
      (node (ref "U16") (pin "14") (pinfunction "V+_14") (pintype "power_in"))
    )
    (net (code "91") (name "VPH-3.3V") (class "Default")
      (node (ref "C100") (pin "1") (pinfunction "1_1") (pintype "passive"))
      (node (ref "C9") (pin "1") (pinfunction "1_1") (pintype "passive"))
      (node (ref "TP25") (pin "TP") (pinfunction "1_TP") (pintype "passive"))
      (node (ref "U1") (pin "19") (pinfunction "VPH-3.3V_19") (pintype "power_in"))
      (node (ref "U5") (pin "10") (pinfunction "OUT_10") (pintype "power_in"))
      (node (ref "U5") (pin "9") (pinfunction "OUTS_9") (pintype "power_in"))
    )
    (net (code "92") (name "VPL-1.6V") (class "Default")
      (node (ref "C101") (pin "1") (pinfunction "1_1") (pintype "passive"))
      (node (ref "C8") (pin "1") (pinfunction "1_1") (pintype "passive"))
      (node (ref "TP24") (pin "TP") (pinfunction "1_TP") (pintype "passive"))
      (node (ref "U1") (pin "18") (pinfunction "VPL-1.6V_18") (pintype "power_in"))
      (node (ref "U4") (pin "10") (pinfunction "OUT_10") (pintype "power_in"))
      (node (ref "U4") (pin "9") (pinfunction "OUTS_9") (pintype "power_in"))
    )
    (net (code "93") (name "VPOS-3.3V") (class "Default")
      (node (ref "C10") (pin "1") (pinfunction "1_1") (pintype "passive"))
      (node (ref "C103") (pin "1") (pinfunction "1_1") (pintype "passive"))
      (node (ref "TP26") (pin "TP") (pinfunction "1_TP") (pintype "passive"))
      (node (ref "U1") (pin "30") (pinfunction "VPOS-3.3V_30") (pintype "power_in"))
      (node (ref "U6") (pin "10") (pinfunction "OUT_10") (pintype "power_in"))
      (node (ref "U6") (pin "9") (pinfunction "OUTS_9") (pintype "power_in"))
    )
    (net (code "94") (name "VPOUT-0.9V") (class "Default")
      (node (ref "C104") (pin "1") (pinfunction "1_1") (pintype "passive"))
      (node (ref "C7") (pin "1") (pinfunction "1_1") (pintype "passive"))
      (node (ref "TP23") (pin "TP") (pinfunction "1_TP") (pintype "passive"))
      (node (ref "U1") (pin "5") (pinfunction "VPOUT-0.9V_5") (pintype "power_in"))
      (node (ref "U2") (pin "10") (pinfunction "OUT_10") (pintype "power_in"))
      (node (ref "U2") (pin "9") (pinfunction "OUTS_9") (pintype "power_in"))
    )
    (net (code "95") (name "unconnected-(J4-Pad1)") (class "Default")
      (node (ref "J4") (pin "1") (pinfunction "1_1") (pintype "passive"))
    )
    (net (code "96") (name "unconnected-(J4-Pad2)") (class "Default")
      (node (ref "J4") (pin "2") (pinfunction "2_2") (pintype "passive"))
    )
    (net (code "97") (name "unconnected-(J4-Pad3)") (class "Default")
      (node (ref "J4") (pin "3") (pinfunction "3_3") (pintype "passive"))
    )
    (net (code "98") (name "unconnected-(J4-Pad4)") (class "Default")
      (node (ref "J4") (pin "4") (pinfunction "4_4") (pintype "passive"))
    )
    (net (code "99") (name "unconnected-(J4-Pad5)") (class "Default")
      (node (ref "J4") (pin "5") (pinfunction "5_5") (pintype "passive"))
    )
    (net (code "100") (name "unconnected-(J4-Pad6)") (class "Default")
      (node (ref "J4") (pin "6") (pinfunction "6_6") (pintype "passive"))
    )
    (net (code "101") (name "unconnected-(J4-Pad7)") (class "Default")
      (node (ref "J4") (pin "7") (pinfunction "7_7") (pintype "passive"))
    )
    (net (code "102") (name "unconnected-(J4-Pad8)") (class "Default")
      (node (ref "J4") (pin "8") (pinfunction "8_8") (pintype "passive"))
    )
    (net (code "103") (name "unconnected-(J4-Pad9)") (class "Default")
      (node (ref "J4") (pin "9") (pinfunction "9_9") (pintype "passive"))
    )
    (net (code "104") (name "unconnected-(J4-Pad10)") (class "Default")
      (node (ref "J4") (pin "10") (pinfunction "10_10") (pintype "passive"))
    )
    (net (code "105") (name "unconnected-(J4-Pad17)") (class "Default")
      (node (ref "J4") (pin "17") (pinfunction "17_17") (pintype "passive"))
    )
    (net (code "106") (name "unconnected-(J4-Pad18)") (class "Default")
      (node (ref "J4") (pin "18") (pinfunction "18_18") (pintype "passive"))
    )
    (net (code "107") (name "unconnected-(J4-Pad19)") (class "Default")
      (node (ref "J4") (pin "19") (pinfunction "19_19") (pintype "passive"))
    )
    (net (code "108") (name "unconnected-(J4-Pad20)") (class "Default")
      (node (ref "J4") (pin "20") (pinfunction "20_20") (pintype "passive"))
    )
    (net (code "109") (name "unconnected-(J4-Pad33)") (class "Default")
      (node (ref "J4") (pin "33") (pinfunction "33_33") (pintype "passive"))
    )
    (net (code "110") (name "unconnected-(J4-Pad34)") (class "Default")
      (node (ref "J4") (pin "34") (pinfunction "34_34") (pintype "passive"))
    )
    (net (code "111") (name "unconnected-(J4-Pad35)") (class "Default")
      (node (ref "J4") (pin "35") (pinfunction "35_35") (pintype "passive"))
    )
    (net (code "112") (name "unconnected-(J4-Pad36)") (class "Default")
      (node (ref "J4") (pin "36") (pinfunction "36_36") (pintype "passive"))
    )
    (net (code "113") (name "unconnected-(R2-Pad8)") (class "Default")
      (node (ref "R2") (pin "8") (pinfunction "8_8") (pintype "passive"))
    )
    (net (code "114") (name "unconnected-(R2-Pad9)") (class "Default")
      (node (ref "R2") (pin "9") (pinfunction "9_9") (pintype "passive"))
    )
    (net (code "115") (name "unconnected-(R20-11-Pad1)") (class "Default")
      (node (ref "R20") (pin "1") (pinfunction "11_1") (pintype "passive"))
    )
    (net (code "116") (name "unconnected-(R20-22-Pad2)") (class "Default")
      (node (ref "R20") (pin "2") (pinfunction "22_2") (pintype "passive"))
    )
    (net (code "117") (name "unconnected-(R20-88-Pad8)") (class "Default")
      (node (ref "R20") (pin "8") (pinfunction "88_8") (pintype "passive"))
    )
    (net (code "118") (name "unconnected-(R20-99-Pad9)") (class "Default")
      (node (ref "R20") (pin "9") (pinfunction "99_9") (pintype "passive"))
    )
    (net (code "119") (name "unconnected-(U1A-ABITOUT-Pad24)") (class "Default")
      (node (ref "U1") (pin "24") (pinfunction "ABITOUT_24") (pintype "output"))
    )
    (net (code "120") (name "~{FAULT}") (class "Default")
      (node (ref "Q2") (pin "3") (pinfunction "D_3") (pintype "passive"))
      (node (ref "R32") (pin "1") (pinfunction "1_1") (pintype "passive"))
      (node (ref "TP45") (pin "TP") (pinfunction "1_TP") (pintype "passive"))
      (node (ref "U16") (pin "7") (pinfunction "IO2_7") (pintype "bidirectional"))
    )
    (net (code "121") (name "~{SD}") (class "Default")
      (node (ref "J4") (pin "39") (pinfunction "39_39") (pintype "passive"))
      (node (ref "J4") (pin "40") (pinfunction "40_40") (pintype "passive"))
    )
  )
)
